# cpu-68010.net
KiCad netlist of a schematic drawn in EAGLE
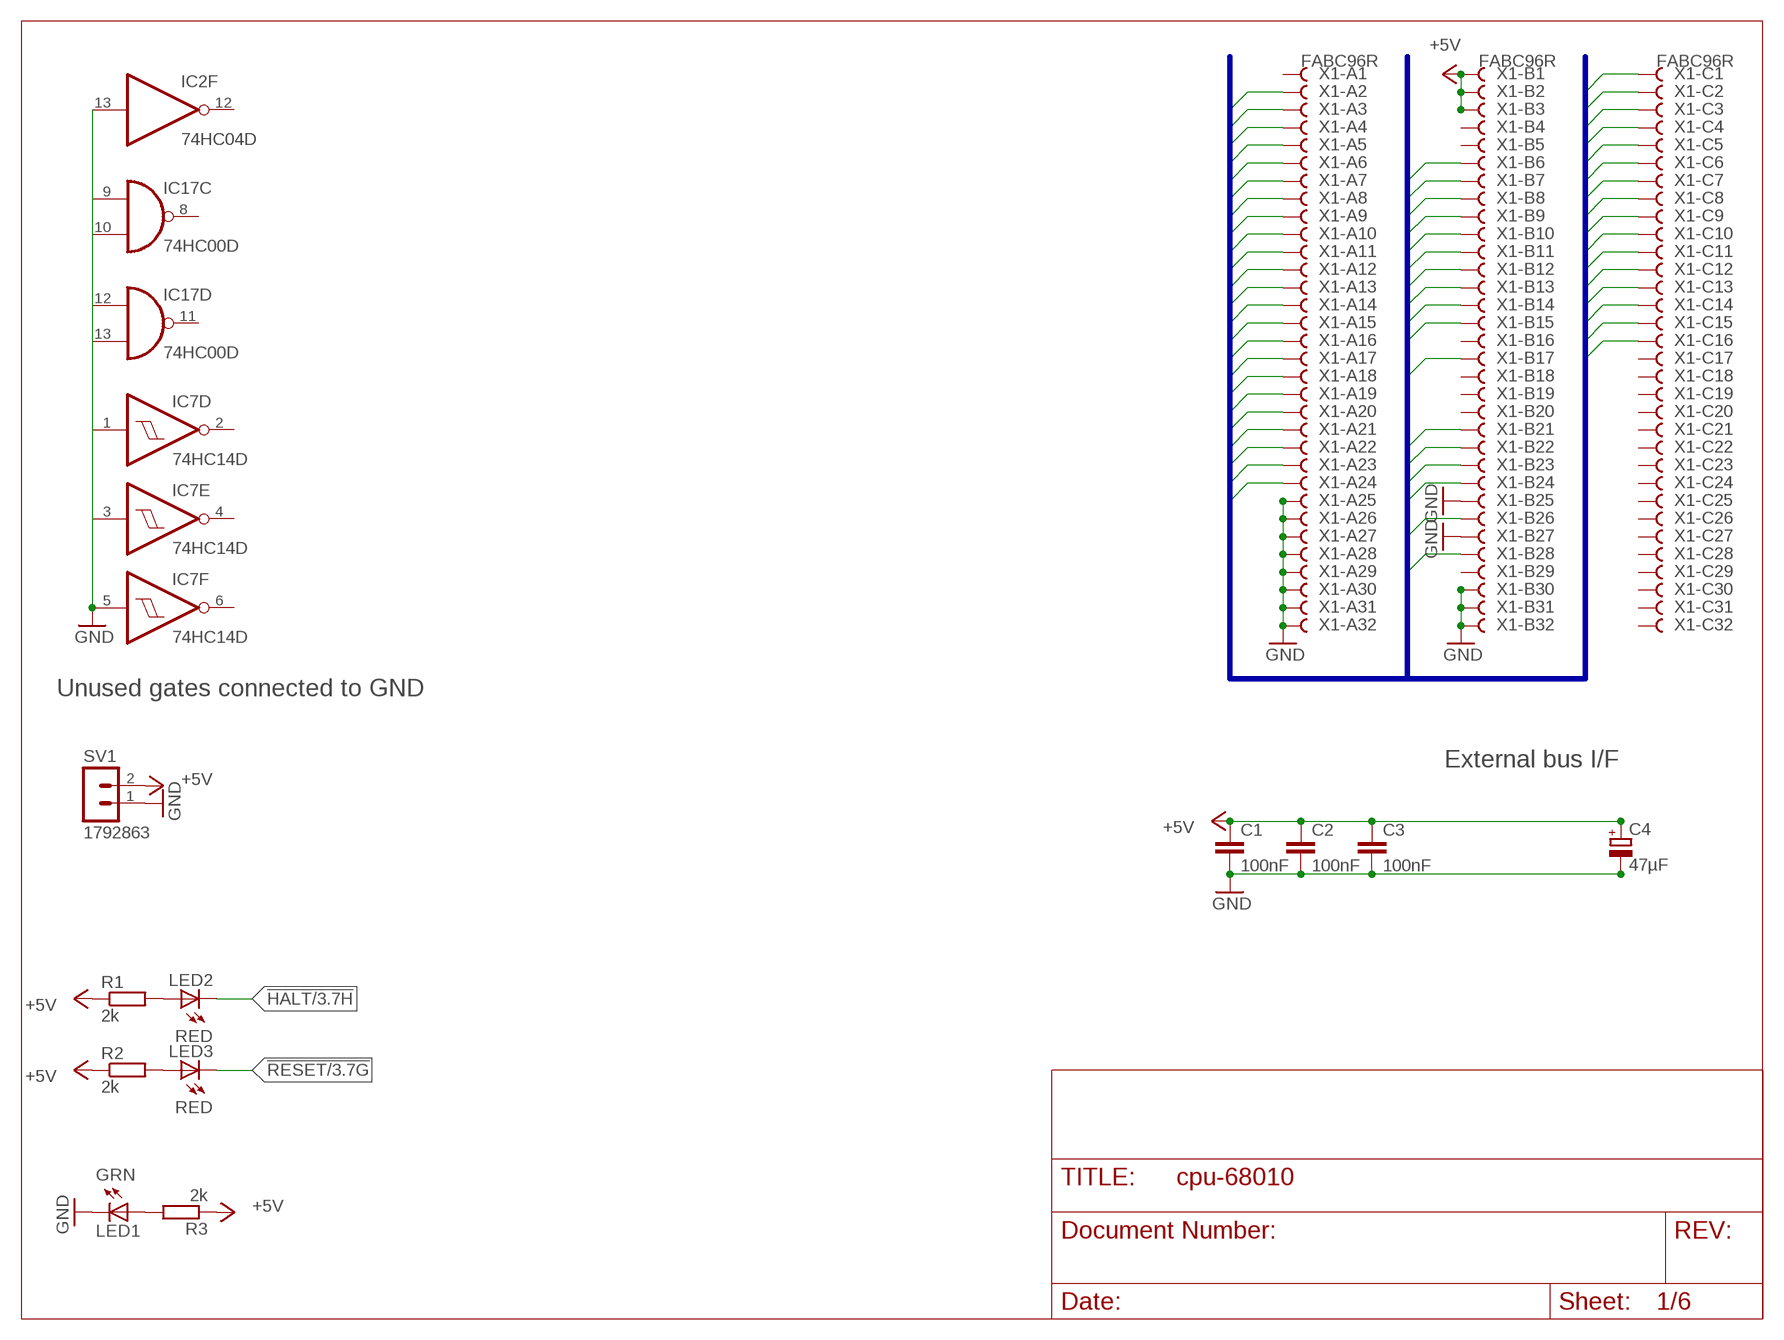
[diagram p0: schematic, sheet 1]
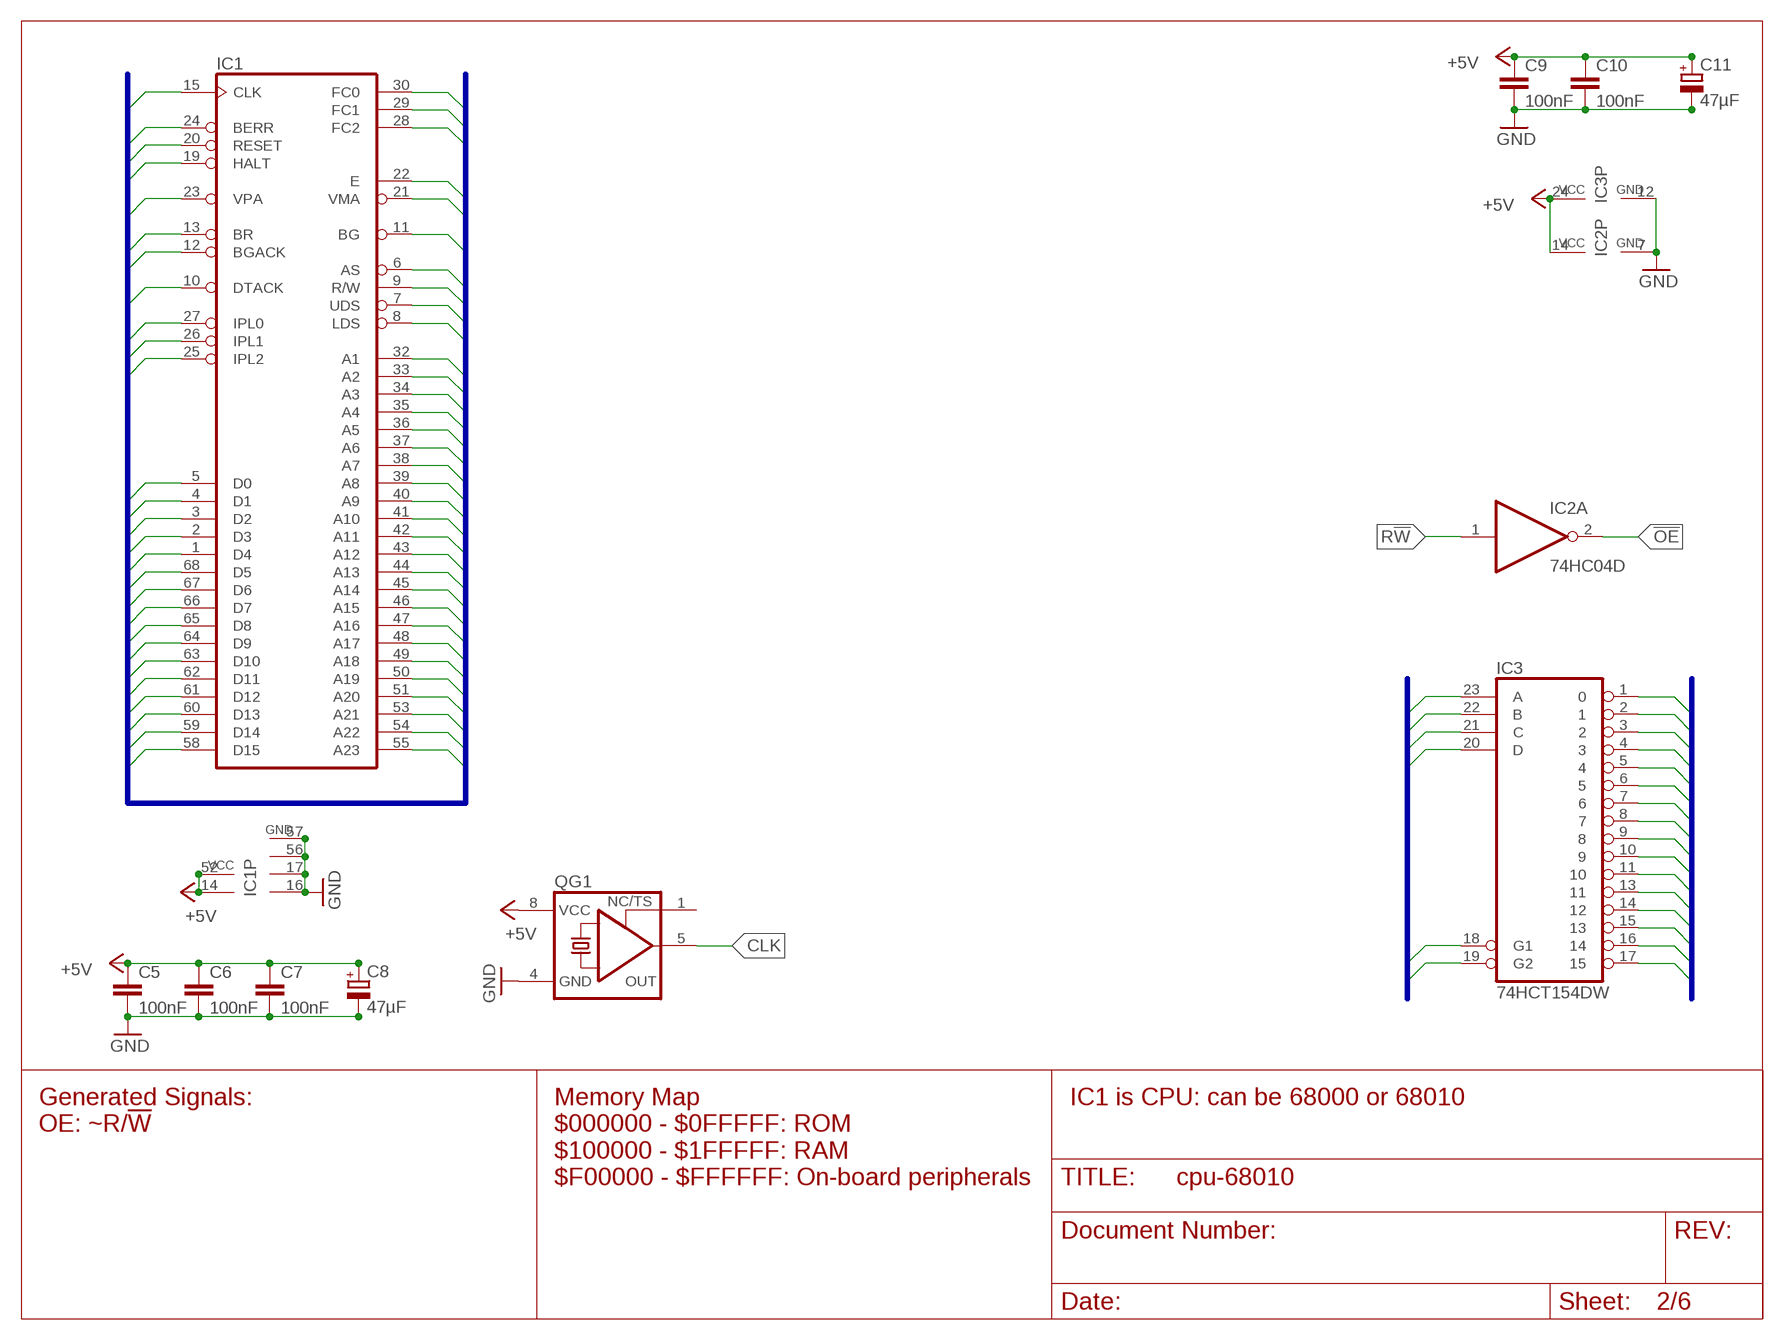
[diagram p1: schematic, sheet 2]
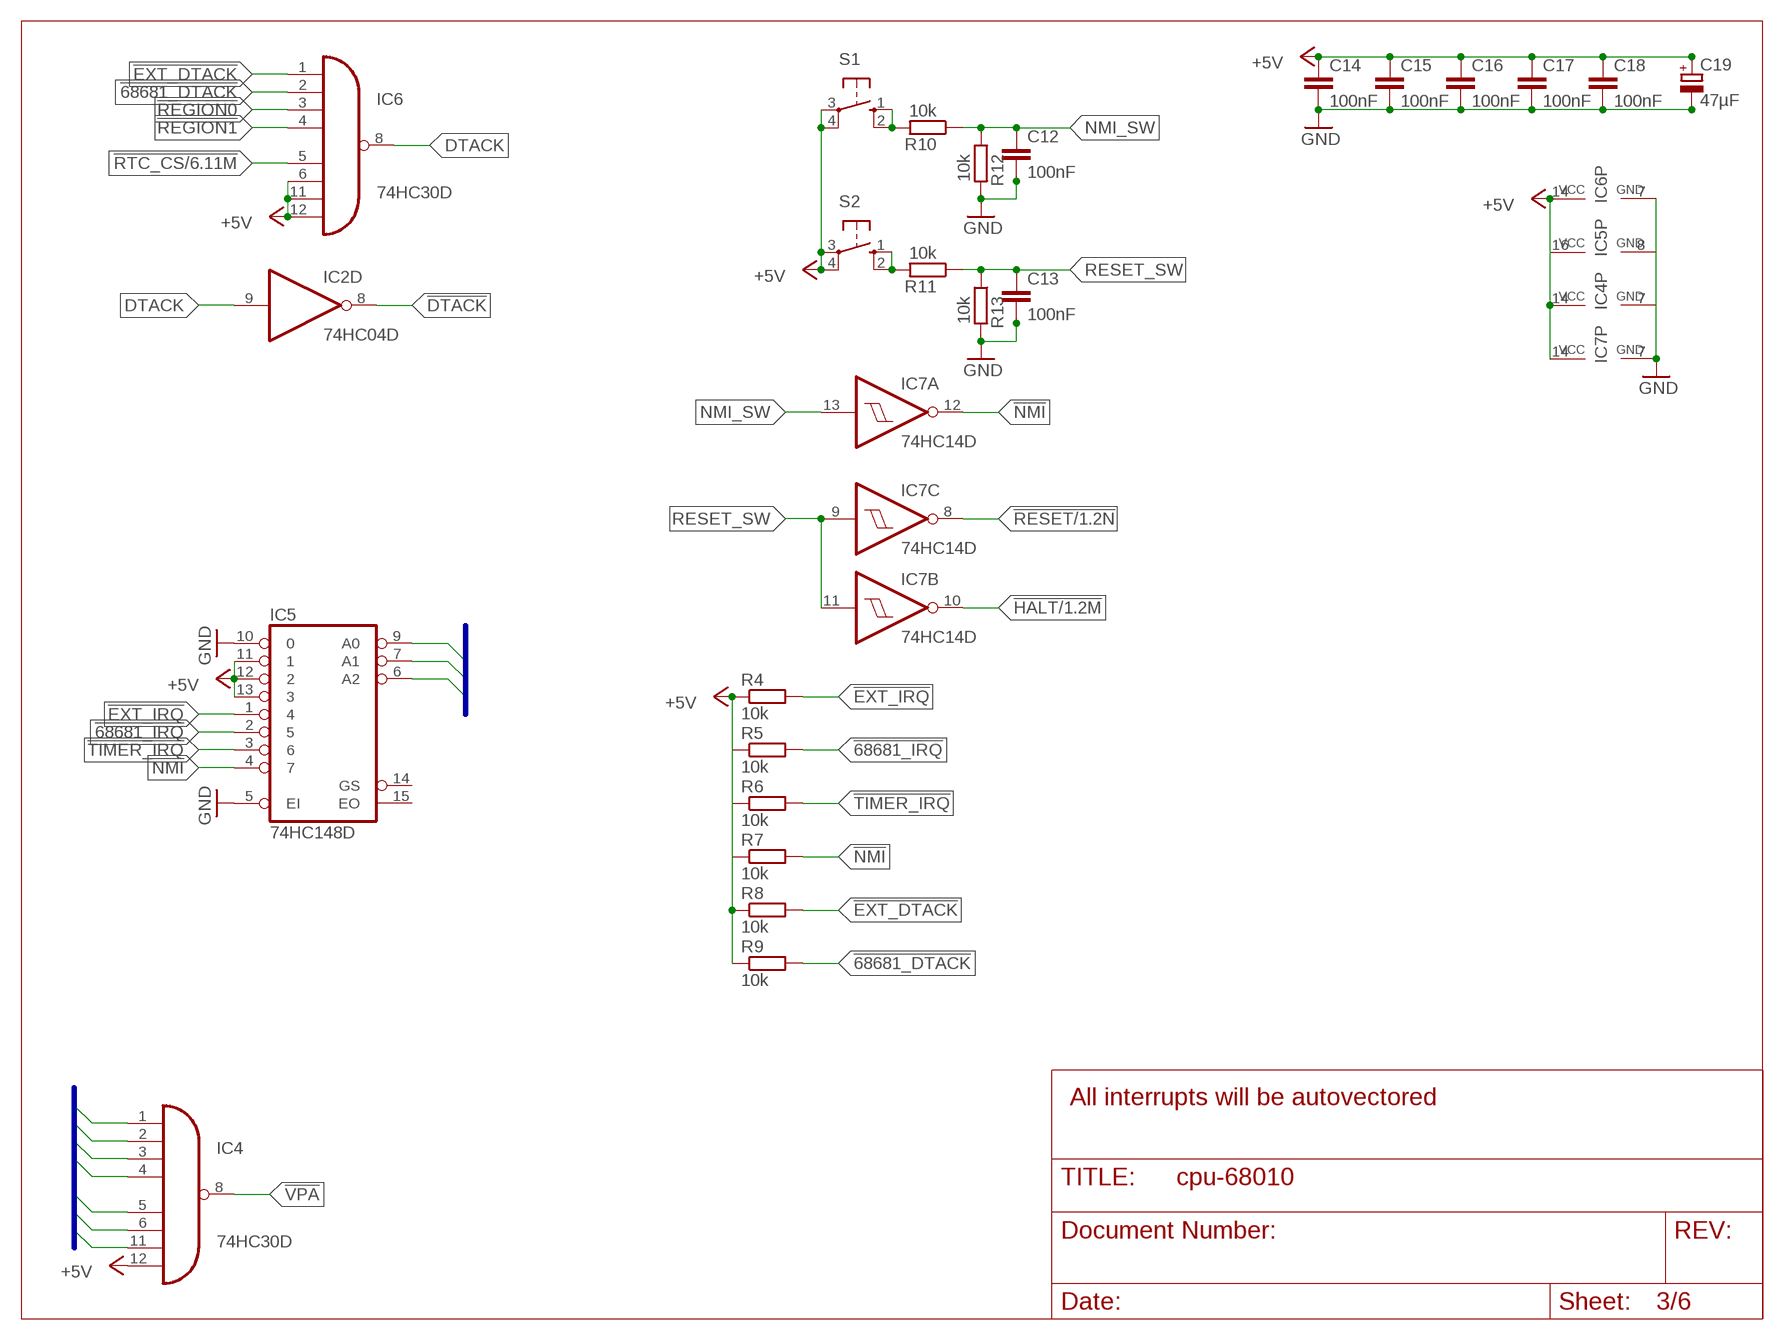
[diagram p2: schematic, sheet 3]
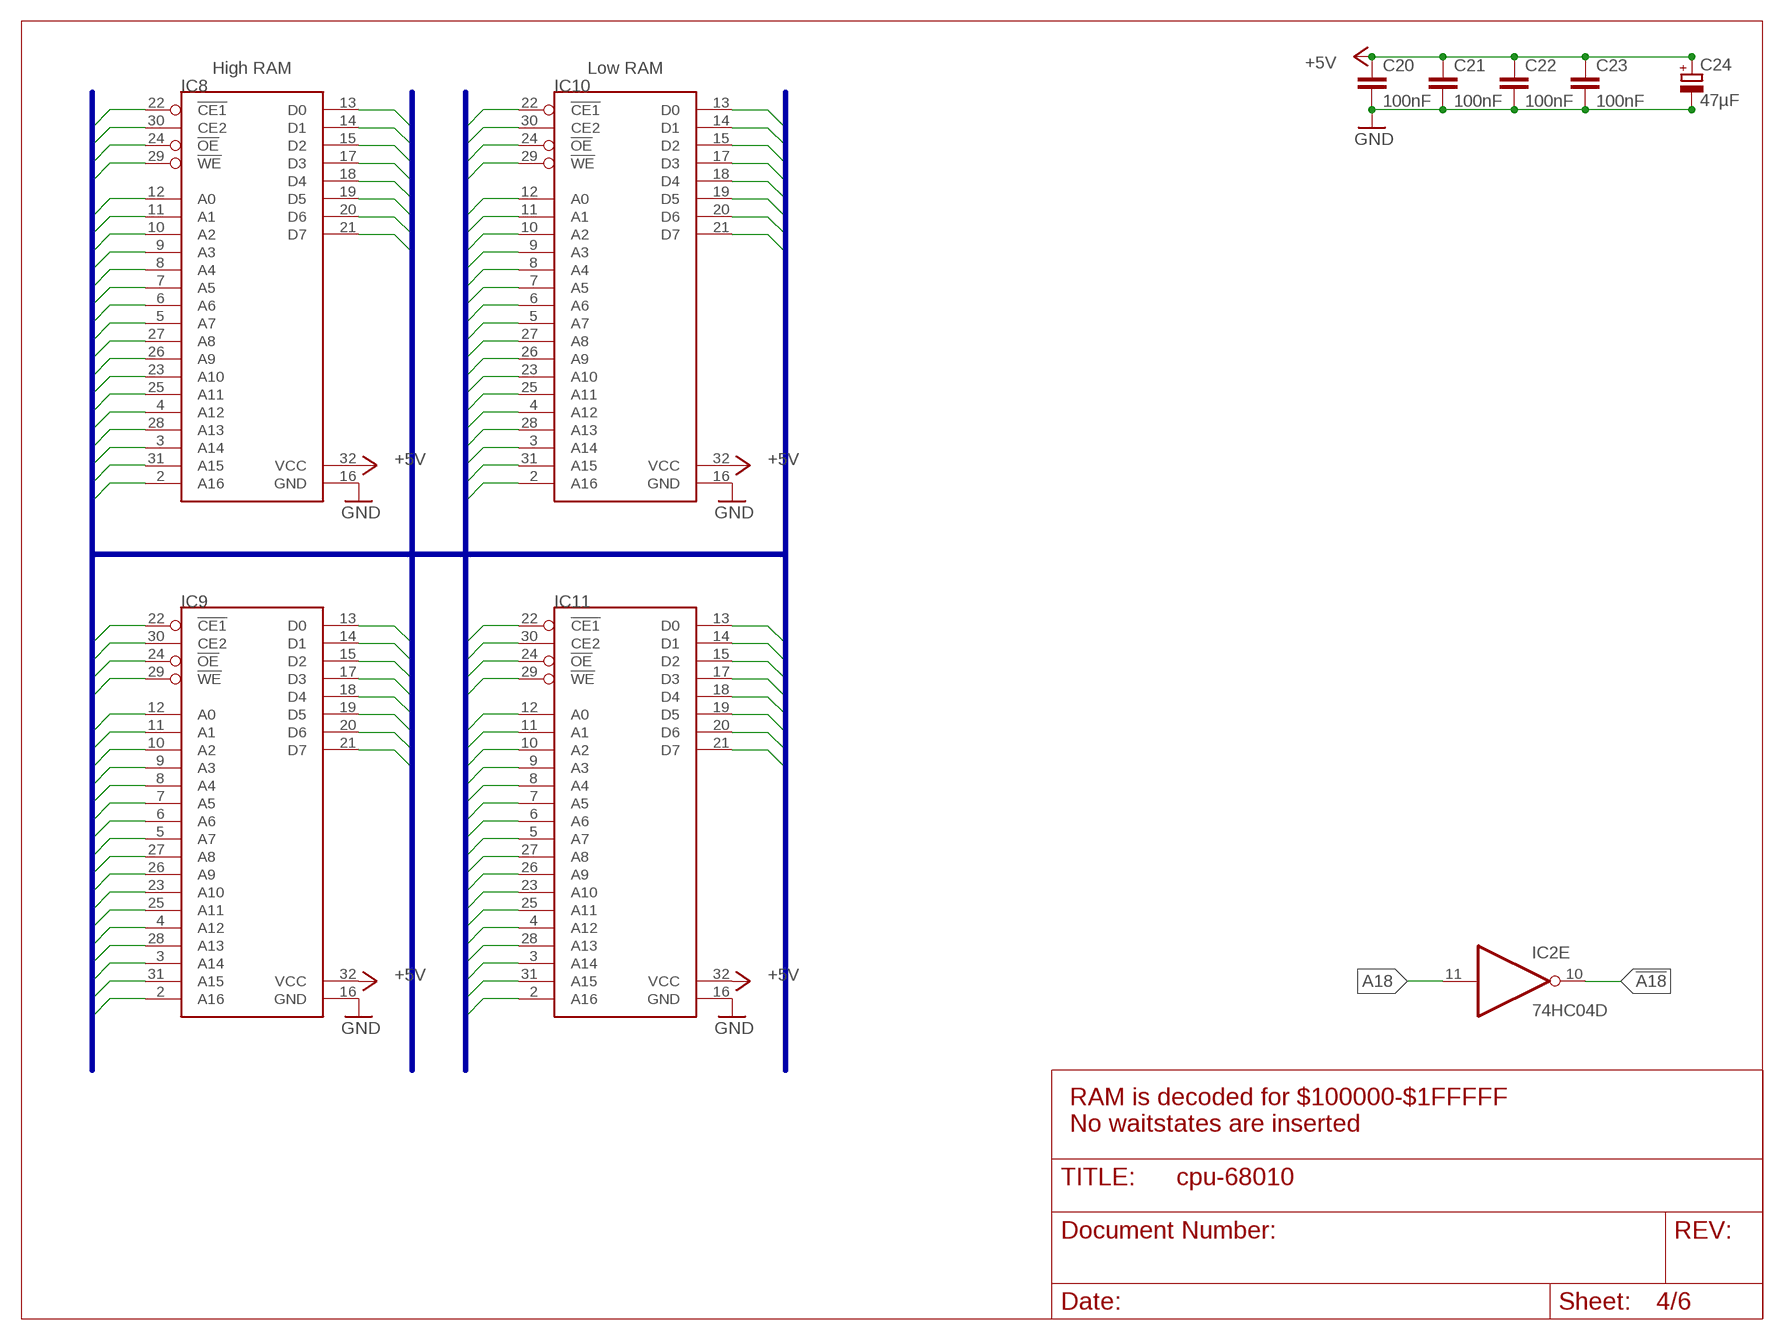
[diagram p3: schematic, sheet 4]
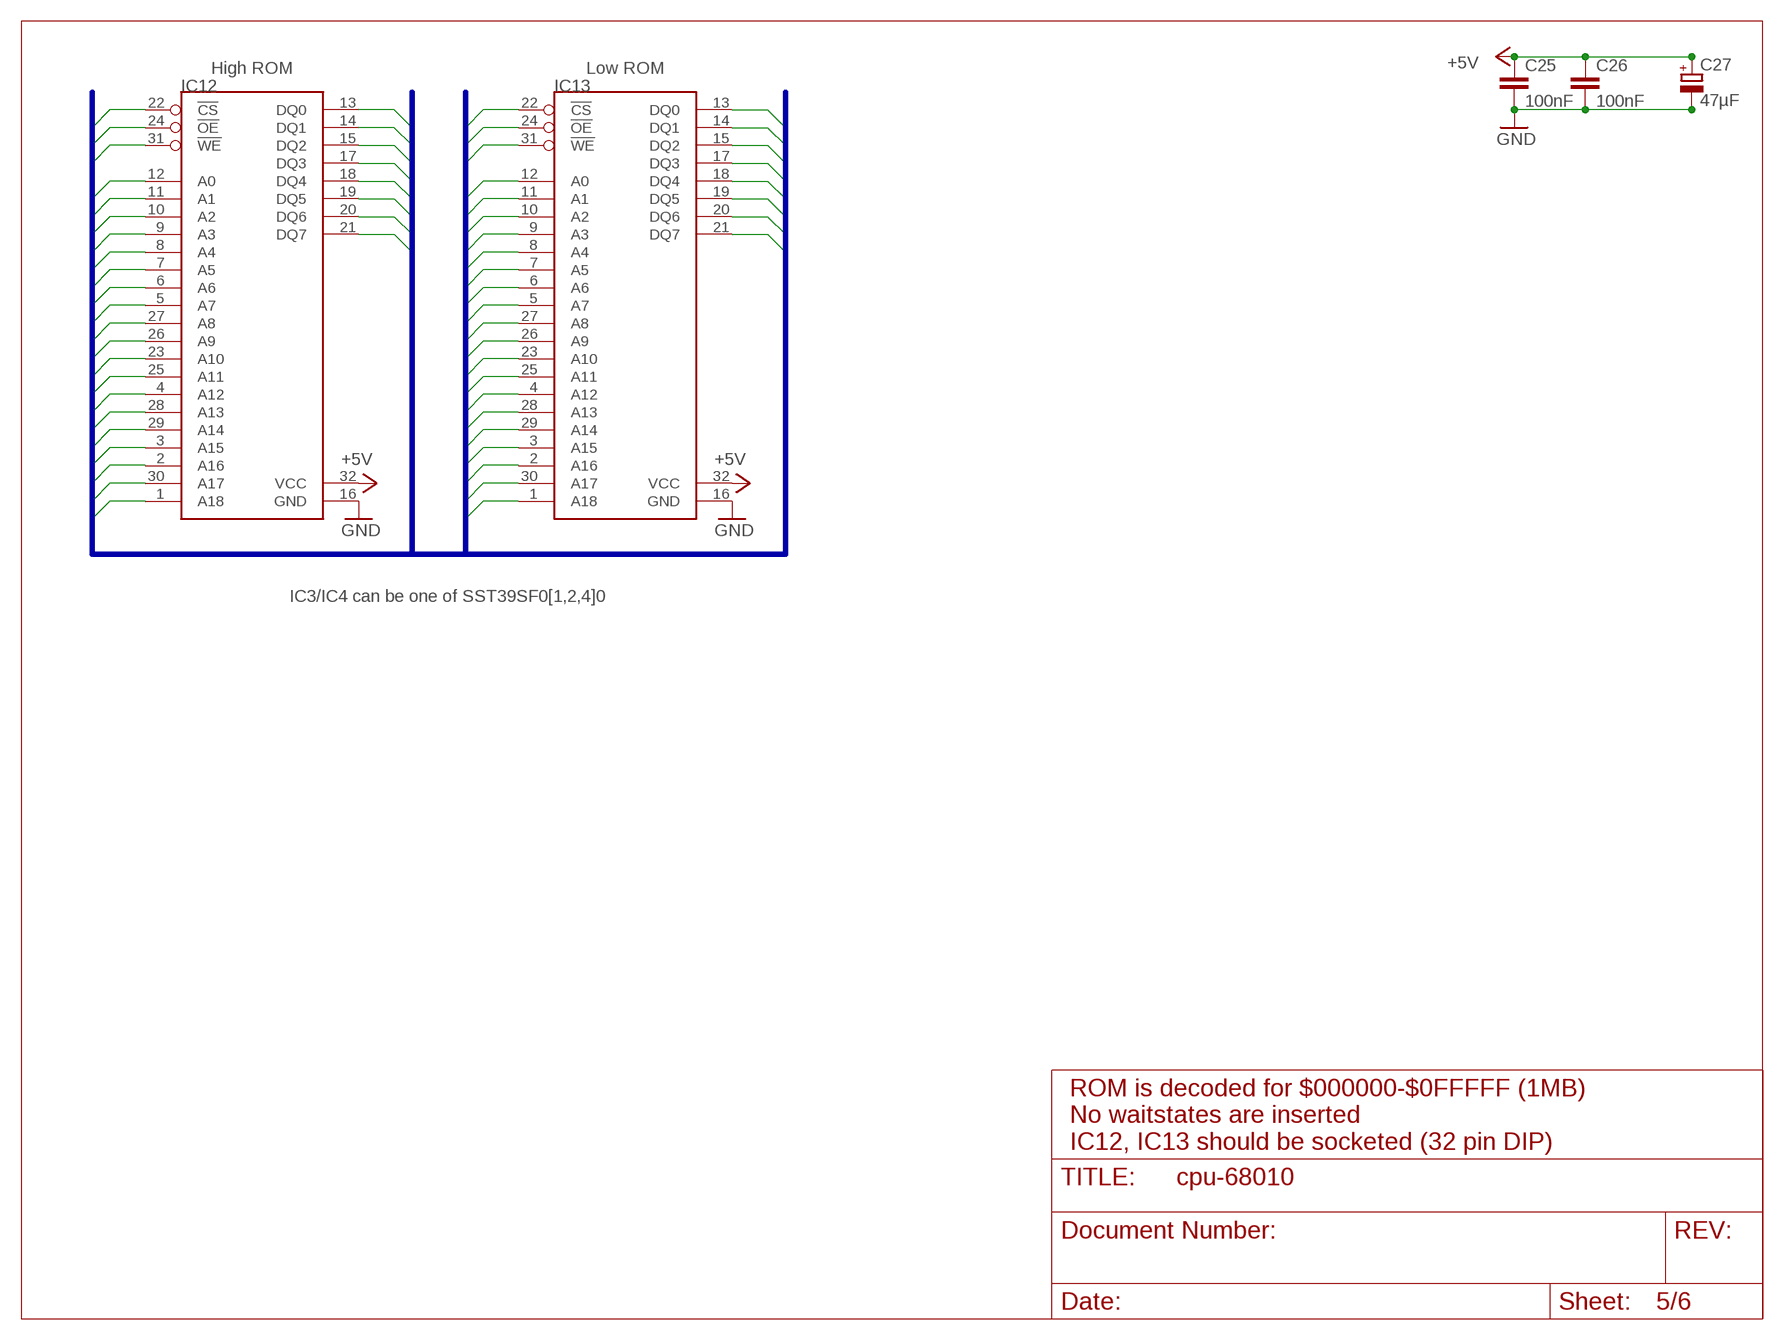
[diagram p4: schematic, sheet 5]
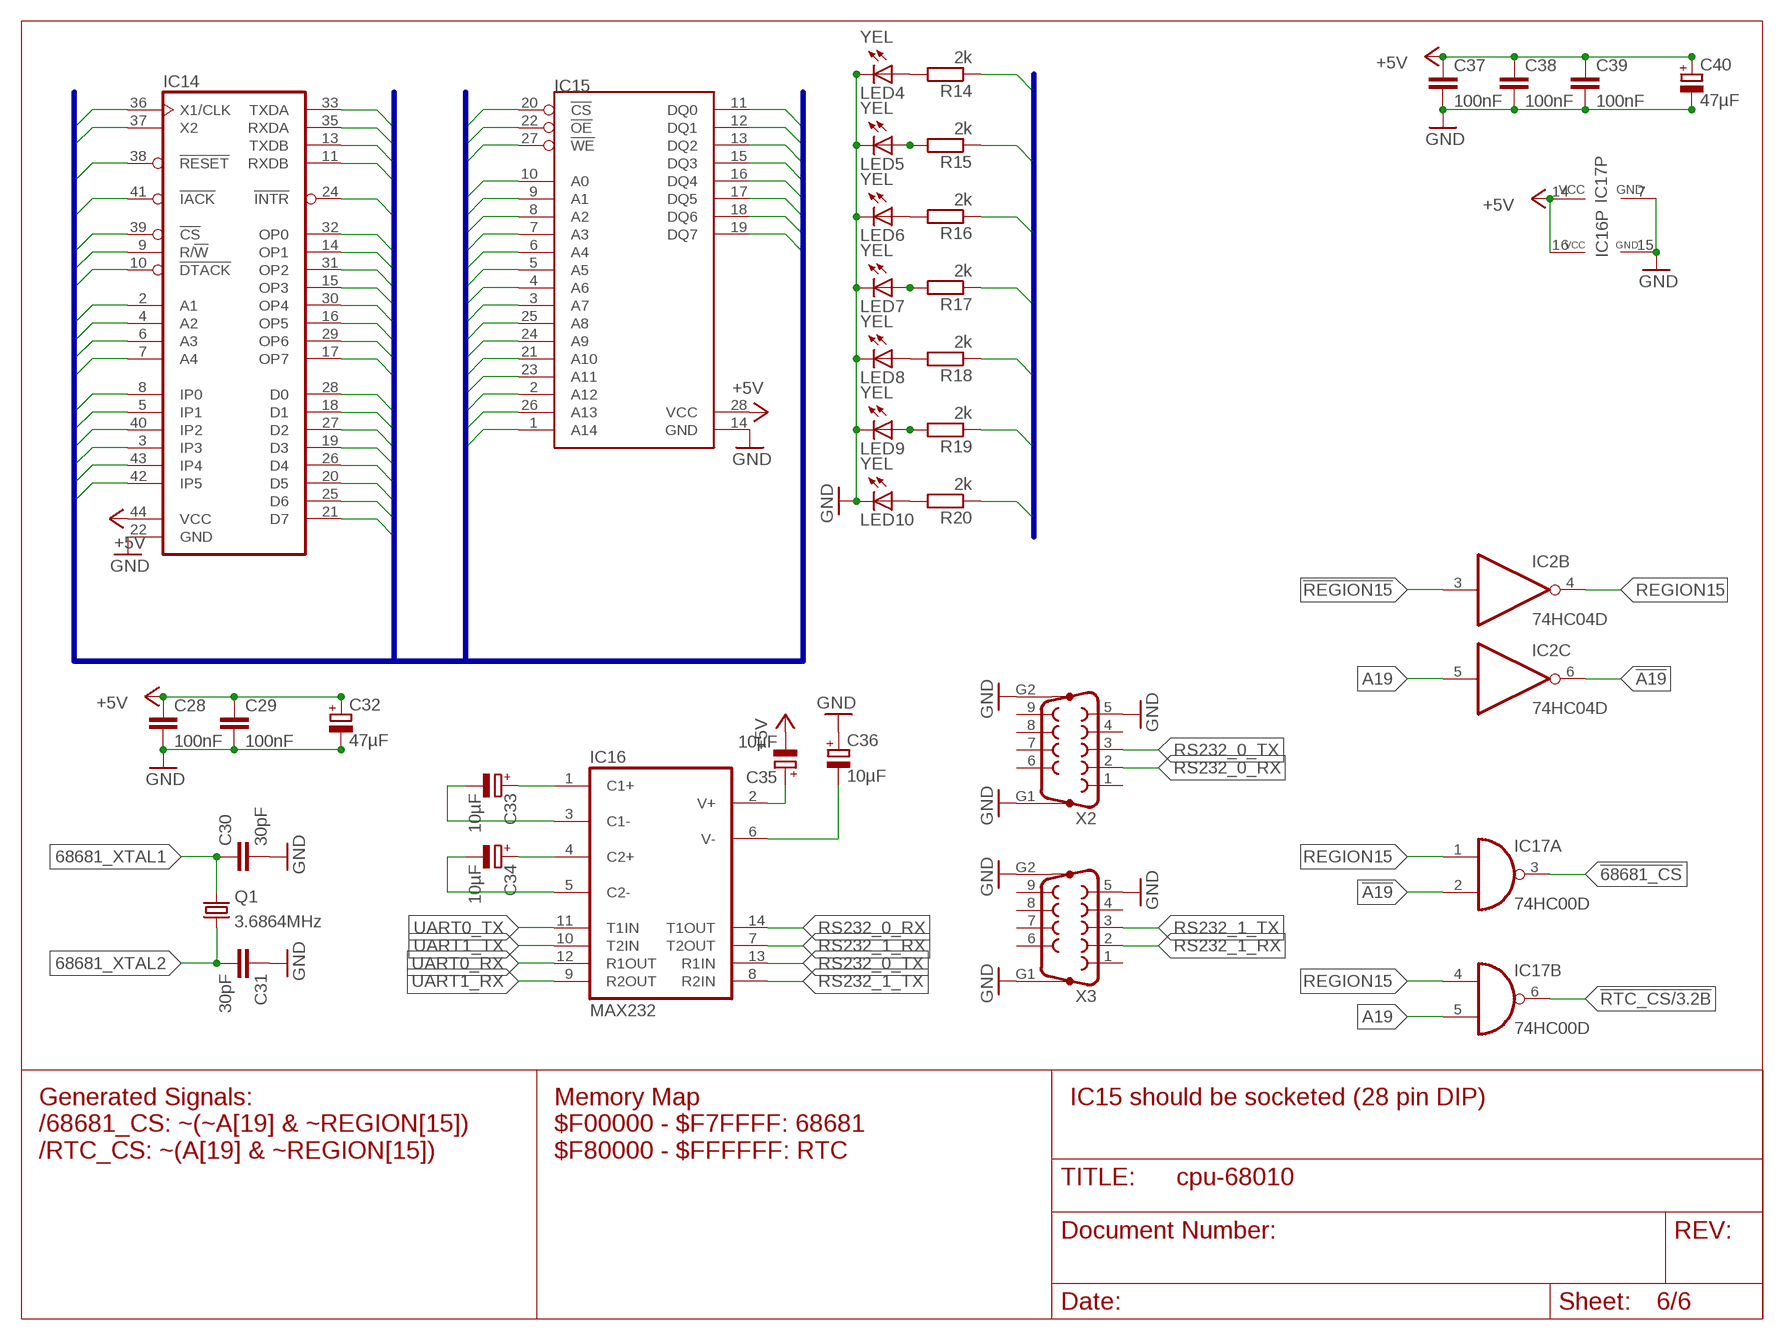
[diagram p5: schematic, sheet 6]

(export (version "E")
  (design (tool "Eeschema 10.0.6"))
  (components
    (comp (ref "C25")
      (value "100nF")
      (footprint "eagle-import:C0805")
      (libsource (lib "eagle-import") (part "C-EUC0805"))
    )
    (comp (ref "C26")
      (value "100nF")
      (footprint "eagle-import:C0805")
      (libsource (lib "eagle-import") (part "C-EUC0805"))
    )
    (comp (ref "C27")
      (value "47µF")
      (footprint "eagle-import:CT6032")
      (libsource (lib "eagle-import") (part "CPOL-EUCT6032"))
    )
    (comp (ref "IC12")
      (value "SST39SF0X0PDIP32")
      (footprint "eagle-import:DIL32")
      (libsource (lib "eagle-import") (part "SST39SF0X0PDIP32"))
    )
    (comp (ref "IC13")
      (value "SST39SF0X0PDIP32")
      (footprint "eagle-import:DIL32")
      (libsource (lib "eagle-import") (part "SST39SF0X0PDIP32"))
    )
    (comp (ref "C28")
      (value "100nF")
      (footprint "eagle-import:C0805")
      (libsource (lib "eagle-import") (part "C-EUC0805"))
    )
    (comp (ref "C29")
      (value "100nF")
      (footprint "eagle-import:C0805")
      (libsource (lib "eagle-import") (part "C-EUC0805"))
    )
    (comp (ref "C30")
      (value "30pF")
      (footprint "eagle-import:C0805")
      (libsource (lib "eagle-import") (part "C-EUC0805"))
    )
    (comp (ref "C31")
      (value "30pF")
      (footprint "eagle-import:C0805")
      (libsource (lib "eagle-import") (part "C-EUC0805"))
    )
    (comp (ref "C32")
      (value "47µF")
      (footprint "eagle-import:CT6032")
      (libsource (lib "eagle-import") (part "CPOL-EUCT6032"))
    )
    (comp (ref "C33")
      (value "10µF")
      (footprint "eagle-import:E1,8-4")
      (libsource (lib "eagle-import") (part "CPOL-EUE1.8-4"))
    )
    (comp (ref "C34")
      (value "10µF")
      (footprint "eagle-import:E1,8-4")
      (libsource (lib "eagle-import") (part "CPOL-EUE1.8-4"))
    )
    (comp (ref "C35")
      (value "10µF")
      (footprint "eagle-import:E1,8-4")
      (libsource (lib "eagle-import") (part "CPOL-EUE1.8-4"))
    )
    (comp (ref "C36")
      (value "10µF")
      (footprint "eagle-import:E1,8-4")
      (libsource (lib "eagle-import") (part "CPOL-EUE1.8-4"))
    )
    (comp (ref "C37")
      (value "100nF")
      (footprint "eagle-import:C0805")
      (libsource (lib "eagle-import") (part "C-EUC0805"))
    )
    (comp (ref "C38")
      (value "100nF")
      (footprint "eagle-import:C0805")
      (libsource (lib "eagle-import") (part "C-EUC0805"))
    )
    (comp (ref "C39")
      (value "100nF")
      (footprint "eagle-import:C0805")
      (libsource (lib "eagle-import") (part "C-EUC0805"))
    )
    (comp (ref "C40")
      (value "47µF")
      (footprint "eagle-import:CT6032")
      (libsource (lib "eagle-import") (part "CPOL-EUCT6032"))
    )
    (comp (ref "IC2")
      (value "74HC04D")
      (footprint "eagle-import:SO14")
      (libsource (lib "eagle-import") (part "7404DHC"))
    )
    (comp (ref "IC14")
      (value "MC68681PLCC44-SOCKET")
      (footprint "eagle-import:PLCC-S44")
      (libsource (lib "eagle-import") (part "MC68681PLCC44-SOCKET"))
    )
    (comp (ref "IC15")
      (value "DS1244EDIP-28")
      (footprint "eagle-import:DIL28-6")
      (libsource (lib "eagle-import") (part "DS1244EDIP-28"))
    )
    (comp (ref "IC16")
      (value "MAX232")
      (footprint "eagle-import:DIL16")
      (fields (field (name "MF") "MAXIM") (field (name "MPN") "MAX232ACPE+"))
      (libsource (lib "eagle-import") (part "MAX232"))
    )
    (comp (ref "IC17")
      (value "74HC00D")
      (footprint "eagle-import:SO14")
      (libsource (lib "eagle-import") (part "7400DHC"))
    )
    (comp (ref "LED4")
      (value "YEL")
      (footprint "eagle-import:CHIPLED_1206")
      (libsource (lib "eagle-import") (part "LEDCHIPLED_1206"))
    )
    (comp (ref "LED5")
      (value "YEL")
      (footprint "eagle-import:CHIPLED_1206")
      (libsource (lib "eagle-import") (part "LEDCHIPLED_1206"))
    )
    (comp (ref "LED6")
      (value "YEL")
      (footprint "eagle-import:CHIPLED_1206")
      (libsource (lib "eagle-import") (part "LEDCHIPLED_1206"))
    )
    (comp (ref "LED7")
      (value "YEL")
      (footprint "eagle-import:CHIPLED_1206")
      (libsource (lib "eagle-import") (part "LEDCHIPLED_1206"))
    )
    (comp (ref "LED8")
      (value "YEL")
      (footprint "eagle-import:CHIPLED_1206")
      (libsource (lib "eagle-import") (part "LEDCHIPLED_1206"))
    )
    (comp (ref "LED9")
      (value "YEL")
      (footprint "eagle-import:CHIPLED_1206")
      (libsource (lib "eagle-import") (part "LEDCHIPLED_1206"))
    )
    (comp (ref "LED10")
      (value "YEL")
      (footprint "eagle-import:CHIPLED_1206")
      (libsource (lib "eagle-import") (part "LEDCHIPLED_1206"))
    )
    (comp (ref "Q1")
      (value "3.6864MHz")
      (footprint "eagle-import:HC49_S")
      (libsource (lib "eagle-import") (part "CRYSTALHC49S"))
    )
    (comp (ref "R14")
      (value "2k")
      (footprint "eagle-import:M0805")
      (libsource (lib "eagle-import") (part "R-EU_M0805"))
    )
    (comp (ref "R15")
      (value "2k")
      (footprint "eagle-import:M0805")
      (libsource (lib "eagle-import") (part "R-EU_M0805"))
    )
    (comp (ref "R16")
      (value "2k")
      (footprint "eagle-import:M0805")
      (libsource (lib "eagle-import") (part "R-EU_M0805"))
    )
    (comp (ref "R17")
      (value "2k")
      (footprint "eagle-import:M0805")
      (libsource (lib "eagle-import") (part "R-EU_M0805"))
    )
    (comp (ref "R18")
      (value "2k")
      (footprint "eagle-import:M0805")
      (libsource (lib "eagle-import") (part "R-EU_M0805"))
    )
    (comp (ref "R19")
      (value "2k")
      (footprint "eagle-import:M0805")
      (libsource (lib "eagle-import") (part "R-EU_M0805"))
    )
    (comp (ref "R20")
      (value "2k")
      (footprint "eagle-import:M0805")
      (libsource (lib "eagle-import") (part "R-EU_M0805"))
    )
    (comp (ref "X2")
      (value "F09HP")
      (footprint "eagle-import:F09HP")
      (libsource (lib "eagle-import") (part "F09HP"))
    )
    (comp (ref "X3")
      (value "F09HP")
      (footprint "eagle-import:F09HP")
      (libsource (lib "eagle-import") (part "F09HP"))
    )
    (comp (ref "C12")
      (value "100nF")
      (footprint "eagle-import:C0805")
      (libsource (lib "eagle-import") (part "C-EUC0805"))
    )
    (comp (ref "C13")
      (value "100nF")
      (footprint "eagle-import:C0805")
      (libsource (lib "eagle-import") (part "C-EUC0805"))
    )
    (comp (ref "C14")
      (value "100nF")
      (footprint "eagle-import:C0805")
      (libsource (lib "eagle-import") (part "C-EUC0805"))
    )
    (comp (ref "C15")
      (value "100nF")
      (footprint "eagle-import:C0805")
      (libsource (lib "eagle-import") (part "C-EUC0805"))
    )
    (comp (ref "C16")
      (value "100nF")
      (footprint "eagle-import:C0805")
      (libsource (lib "eagle-import") (part "C-EUC0805"))
    )
    (comp (ref "C17")
      (value "100nF")
      (footprint "eagle-import:C0805")
      (libsource (lib "eagle-import") (part "C-EUC0805"))
    )
    (comp (ref "C18")
      (value "100nF")
      (footprint "eagle-import:C0805")
      (libsource (lib "eagle-import") (part "C-EUC0805"))
    )
    (comp (ref "C19")
      (value "47µF")
      (footprint "eagle-import:CT6032")
      (libsource (lib "eagle-import") (part "CPOL-EUCT6032"))
    )
    (comp (ref "IC4")
      (value "74HC30D")
      (footprint "eagle-import:SO14")
      (libsource (lib "eagle-import") (part "7430DHC"))
    )
    (comp (ref "IC5")
      (value "74HC148D")
      (footprint "eagle-import:SO16")
      (libsource (lib "eagle-import") (part "74148DHC"))
    )
    (comp (ref "IC6")
      (value "74HC30D")
      (footprint "eagle-import:SO14")
      (libsource (lib "eagle-import") (part "7430DHC"))
    )
    (comp (ref "IC7")
      (value "74HC14D")
      (footprint "eagle-import:SO14")
      (libsource (lib "eagle-import") (part "7414DHC"))
    )
    (comp (ref "R4")
      (value "10k")
      (footprint "eagle-import:M0805")
      (libsource (lib "eagle-import") (part "R-EU_M0805"))
    )
    (comp (ref "R5")
      (value "10k")
      (footprint "eagle-import:M0805")
      (libsource (lib "eagle-import") (part "R-EU_M0805"))
    )
    (comp (ref "R6")
      (value "10k")
      (footprint "eagle-import:M0805")
      (libsource (lib "eagle-import") (part "R-EU_M0805"))
    )
    (comp (ref "R7")
      (value "10k")
      (footprint "eagle-import:M0805")
      (libsource (lib "eagle-import") (part "R-EU_M0805"))
    )
    (comp (ref "R8")
      (value "10k")
      (footprint "eagle-import:M0805")
      (libsource (lib "eagle-import") (part "R-EU_M0805"))
    )
    (comp (ref "R9")
      (value "10k")
      (footprint "eagle-import:M0805")
      (libsource (lib "eagle-import") (part "R-EU_M0805"))
    )
    (comp (ref "R10")
      (value "10k")
      (footprint "eagle-import:M0805")
      (libsource (lib "eagle-import") (part "R-EU_M0805"))
    )
    (comp (ref "R11")
      (value "10k")
      (footprint "eagle-import:M0805")
      (libsource (lib "eagle-import") (part "R-EU_M0805"))
    )
    (comp (ref "R12")
      (value "10k")
      (footprint "eagle-import:M0805")
      (libsource (lib "eagle-import") (part "R-EU_M0805"))
    )
    (comp (ref "R13")
      (value "10k")
      (footprint "eagle-import:M0805")
      (libsource (lib "eagle-import") (part "R-EU_M0805"))
    )
    (comp (ref "S1")
      (value "10-XX")
      (footprint "eagle-import:B3F-10XX")
      (fields (field (name "MPN") "B3F-1000"))
      (libsource (lib "eagle-import") (part "10-XX"))
    )
    (comp (ref "S2")
      (value "10-XX")
      (footprint "eagle-import:B3F-10XX")
      (fields (field (name "MPN") "B3F-1000"))
      (libsource (lib "eagle-import") (part "10-XX"))
    )
    (comp (ref "C20")
      (value "100nF")
      (footprint "eagle-import:C0805")
      (libsource (lib "eagle-import") (part "C-EUC0805"))
    )
    (comp (ref "C21")
      (value "100nF")
      (footprint "eagle-import:C0805")
      (libsource (lib "eagle-import") (part "C-EUC0805"))
    )
    (comp (ref "C22")
      (value "100nF")
      (footprint "eagle-import:C0805")
      (libsource (lib "eagle-import") (part "C-EUC0805"))
    )
    (comp (ref "C23")
      (value "100nF")
      (footprint "eagle-import:C0805")
      (libsource (lib "eagle-import") (part "C-EUC0805"))
    )
    (comp (ref "C24")
      (value "47µF")
      (footprint "eagle-import:CT6032")
      (libsource (lib "eagle-import") (part "CPOL-EUCT6032"))
    )
    (comp (ref "IC8")
      (value "CY62128BSOIC32")
      (footprint "eagle-import:SO32X")
      (libsource (lib "eagle-import") (part "CY62128BSOIC32"))
    )
    (comp (ref "IC9")
      (value "CY62128BSOIC32")
      (footprint "eagle-import:SO32X")
      (libsource (lib "eagle-import") (part "CY62128BSOIC32"))
    )
    (comp (ref "IC10")
      (value "CY62128BSOIC32")
      (footprint "eagle-import:SO32X")
      (libsource (lib "eagle-import") (part "CY62128BSOIC32"))
    )
    (comp (ref "IC11")
      (value "CY62128BSOIC32")
      (footprint "eagle-import:SO32X")
      (libsource (lib "eagle-import") (part "CY62128BSOIC32"))
    )
    (comp (ref "C1")
      (value "100nF")
      (footprint "eagle-import:C0805")
      (libsource (lib "eagle-import") (part "C-EUC0805"))
    )
    (comp (ref "C2")
      (value "100nF")
      (footprint "eagle-import:C0805")
      (libsource (lib "eagle-import") (part "C-EUC0805"))
    )
    (comp (ref "C3")
      (value "100nF")
      (footprint "eagle-import:C0805")
      (libsource (lib "eagle-import") (part "C-EUC0805"))
    )
    (comp (ref "C4")
      (value "47µF")
      (footprint "eagle-import:CT6032")
      (libsource (lib "eagle-import") (part "CPOL-EUCT6032"))
    )
    (comp (ref "LED1")
      (value "GRN")
      (footprint "eagle-import:CHIPLED_1206")
      (libsource (lib "eagle-import") (part "LEDCHIPLED_1206"))
    )
    (comp (ref "LED2")
      (value "RED")
      (footprint "eagle-import:CHIPLED_1206")
      (libsource (lib "eagle-import") (part "LEDCHIPLED_1206"))
    )
    (comp (ref "LED3")
      (value "RED")
      (footprint "eagle-import:CHIPLED_1206")
      (libsource (lib "eagle-import") (part "LEDCHIPLED_1206"))
    )
    (comp (ref "R1")
      (value "2k")
      (footprint "eagle-import:M0805")
      (libsource (lib "eagle-import") (part "R-EU_M0805"))
    )
    (comp (ref "R2")
      (value "2k")
      (footprint "eagle-import:M0805")
      (libsource (lib "eagle-import") (part "R-EU_M0805"))
    )
    (comp (ref "R3")
      (value "2k")
      (footprint "eagle-import:M0805")
      (libsource (lib "eagle-import") (part "R-EU_M0805"))
    )
    (comp (ref "SV1")
      (value "1792863")
      (footprint "eagle-import:1792863")
      (libsource (lib "eagle-import") (part "1792863"))
    )
    (comp (ref "X1")
      (value "FABC96R")
      (footprint "eagle-import:FABC96R")
      (libsource (lib "eagle-import") (part "FABC96R"))
    )
    (comp (ref "C5")
      (value "100nF")
      (footprint "eagle-import:C0805")
      (libsource (lib "eagle-import") (part "C-EUC0805"))
    )
    (comp (ref "C6")
      (value "100nF")
      (footprint "eagle-import:C0805")
      (libsource (lib "eagle-import") (part "C-EUC0805"))
    )
    (comp (ref "C7")
      (value "100nF")
      (footprint "eagle-import:C0805")
      (libsource (lib "eagle-import") (part "C-EUC0805"))
    )
    (comp (ref "C8")
      (value "47µF")
      (footprint "eagle-import:CT6032")
      (libsource (lib "eagle-import") (part "CPOL-EUCT6032"))
    )
    (comp (ref "C9")
      (value "100nF")
      (footprint "eagle-import:C0805")
      (libsource (lib "eagle-import") (part "C-EUC0805"))
    )
    (comp (ref "C10")
      (value "100nF")
      (footprint "eagle-import:C0805")
      (libsource (lib "eagle-import") (part "C-EUC0805"))
    )
    (comp (ref "C11")
      (value "47µF")
      (footprint "eagle-import:CT6032")
      (libsource (lib "eagle-import") (part "CPOL-EUCT6032"))
    )
    (comp (ref "IC1")
      (value "MC68000FN-SOC")
      (footprint "eagle-import:PLCC68SOCK")
      (libsource (lib "eagle-import") (part "MC68000FN-SOC"))
    )
    (comp (ref "IC3")
      (value "74HCT154DW")
      (footprint "eagle-import:SO24W")
      (libsource (lib "eagle-import") (part "74154DWHCT"))
    )
    (comp (ref "QG1")
      (value "XO-8")
      (footprint "eagle-import:DIL08S")
      (libsource (lib "eagle-import") (part "XO-8"))
    )
  )
  (nets
    (net (code "1") (name "+5V") (class "Default")
      (node (ref "C1") (pin "1") (pinfunction "1_1") (pintype "passive"))
      (node (ref "C10") (pin "1") (pinfunction "1_1") (pintype "passive"))
      (node (ref "C11") (pin "+") (pinfunction "+_+") (pintype "passive"))
      (node (ref "C14") (pin "1") (pinfunction "1_1") (pintype "passive"))
      (node (ref "C15") (pin "1") (pinfunction "1_1") (pintype "passive"))
      (node (ref "C16") (pin "1") (pinfunction "1_1") (pintype "passive"))
      (node (ref "C17") (pin "1") (pinfunction "1_1") (pintype "passive"))
      (node (ref "C18") (pin "1") (pinfunction "1_1") (pintype "passive"))
      (node (ref "C19") (pin "+") (pinfunction "+_+") (pintype "passive"))
      (node (ref "C2") (pin "1") (pinfunction "1_1") (pintype "passive"))
      (node (ref "C20") (pin "1") (pinfunction "1_1") (pintype "passive"))
      (node (ref "C21") (pin "1") (pinfunction "1_1") (pintype "passive"))
      (node (ref "C22") (pin "1") (pinfunction "1_1") (pintype "passive"))
      (node (ref "C23") (pin "1") (pinfunction "1_1") (pintype "passive"))
      (node (ref "C24") (pin "+") (pinfunction "+_+") (pintype "passive"))
      (node (ref "C25") (pin "1") (pinfunction "1_1") (pintype "passive"))
      (node (ref "C26") (pin "1") (pinfunction "1_1") (pintype "passive"))
      (node (ref "C27") (pin "+") (pinfunction "+_+") (pintype "passive"))
      (node (ref "C28") (pin "1") (pinfunction "1_1") (pintype "passive"))
      (node (ref "C29") (pin "1") (pinfunction "1_1") (pintype "passive"))
      (node (ref "C3") (pin "1") (pinfunction "1_1") (pintype "passive"))
      (node (ref "C32") (pin "+") (pinfunction "+_+") (pintype "passive"))
      (node (ref "C35") (pin "-") (pinfunction "-_-") (pintype "passive"))
      (node (ref "C37") (pin "1") (pinfunction "1_1") (pintype "passive"))
      (node (ref "C38") (pin "1") (pinfunction "1_1") (pintype "passive"))
      (node (ref "C39") (pin "1") (pinfunction "1_1") (pintype "passive"))
      (node (ref "C4") (pin "+") (pinfunction "+_+") (pintype "passive"))
      (node (ref "C40") (pin "+") (pinfunction "+_+") (pintype "passive"))
      (node (ref "C5") (pin "1") (pinfunction "1_1") (pintype "passive"))
      (node (ref "C6") (pin "1") (pinfunction "1_1") (pintype "passive"))
      (node (ref "C7") (pin "1") (pinfunction "1_1") (pintype "passive"))
      (node (ref "C8") (pin "+") (pinfunction "+_+") (pintype "passive"))
      (node (ref "C9") (pin "1") (pinfunction "1_1") (pintype "passive"))
      (node (ref "IC1") (pin "14") (pinfunction "VCC_14") (pintype "power_in"))
      (node (ref "IC1") (pin "52") (pinfunction "VCC_52") (pintype "power_in"))
      (node (ref "IC10") (pin "32") (pinfunction "VCC_32") (pintype "power_in"))
      (node (ref "IC11") (pin "32") (pinfunction "VCC_32") (pintype "power_in"))
      (node (ref "IC12") (pin "32") (pinfunction "VCC_32") (pintype "power_in"))
      (node (ref "IC13") (pin "32") (pinfunction "VCC_32") (pintype "power_in"))
      (node (ref "IC14") (pin "44") (pinfunction "VCC_44") (pintype "power_in"))
      (node (ref "IC15") (pin "28") (pinfunction "VCC_28") (pintype "power_in"))
      (node (ref "IC16") (pin "16") (pinfunction "VCC_16") (pintype "power_in"))
      (node (ref "IC17") (pin "14") (pinfunction "VCC_14") (pintype "power_in"))
      (node (ref "IC2") (pin "14") (pinfunction "VCC_14") (pintype "power_in"))
      (node (ref "IC3") (pin "24") (pinfunction "VCC_24") (pintype "power_in"))
      (node (ref "IC4") (pin "12") (pinfunction "I7_12") (pintype "input"))
      (node (ref "IC4") (pin "14") (pinfunction "VCC_14") (pintype "power_in"))
      (node (ref "IC5") (pin "11") (pinfunction "1_11") (pintype "input"))
      (node (ref "IC5") (pin "12") (pinfunction "2_12") (pintype "input"))
      (node (ref "IC5") (pin "13") (pinfunction "3_13") (pintype "input"))
      (node (ref "IC5") (pin "16") (pinfunction "VCC_16") (pintype "power_in"))
      (node (ref "IC6") (pin "11") (pinfunction "I6_11") (pintype "input"))
      (node (ref "IC6") (pin "12") (pinfunction "I7_12") (pintype "input"))
      (node (ref "IC6") (pin "14") (pinfunction "VCC_14") (pintype "power_in"))
      (node (ref "IC6") (pin "6") (pinfunction "I5_6") (pintype "input"))
      (node (ref "IC7") (pin "14") (pinfunction "VCC_14") (pintype "power_in"))
      (node (ref "IC8") (pin "32") (pinfunction "VCC_32") (pintype "power_in"))
      (node (ref "IC9") (pin "32") (pinfunction "VCC_32") (pintype "power_in"))
      (node (ref "QG1") (pin "8") (pinfunction "VCC_8") (pintype "power_in"))
      (node (ref "R1") (pin "1") (pinfunction "1_1") (pintype "passive"))
      (node (ref "R2") (pin "1") (pinfunction "1_1") (pintype "passive"))
      (node (ref "R3") (pin "1") (pinfunction "1_1") (pintype "passive"))
      (node (ref "R4") (pin "1") (pinfunction "1_1") (pintype "passive"))
      (node (ref "R8") (pin "1") (pinfunction "1_1") (pintype "passive"))
      (node (ref "R9") (pin "1") (pinfunction "1_1") (pintype "passive"))
      (node (ref "S1") (pin "3") (pinfunction "P_3") (pintype "passive"))
      (node (ref "S1") (pin "4") (pinfunction "P1_4") (pintype "passive"))
      (node (ref "S2") (pin "3") (pinfunction "P_3") (pintype "passive"))
      (node (ref "S2") (pin "4") (pinfunction "P1_4") (pintype "passive"))
      (node (ref "SV1") (pin "2") (pinfunction "2_2") (pintype "passive"))
      (node (ref "X1") (pin "B1") (pinfunction "B_B1") (pintype "passive"))
      (node (ref "X1") (pin "B2") (pinfunction "B_B2") (pintype "passive"))
      (node (ref "X1") (pin "B3") (pinfunction "B_B3") (pintype "passive"))
    )
    (net (code "3") (name "68681_XTAL1") (class "Default")
      (node (ref "C30") (pin "1") (pinfunction "1_1") (pintype "passive"))
      (node (ref "IC14") (pin "36") (pinfunction "X1/CLK_36") (pintype "input"))
      (node (ref "Q1") (pin "2") (pinfunction "2_2") (pintype "passive"))
    )
    (net (code "4") (name "68681_XTAL2") (class "Default")
      (node (ref "C31") (pin "2") (pinfunction "2_2") (pintype "passive"))
      (node (ref "IC14") (pin "37") (pinfunction "X2_37") (pintype "output"))
      (node (ref "Q1") (pin "1") (pinfunction "1_1") (pintype "passive"))
    )
    (net (code "5") (name "A1") (class "Default")
      (node (ref "IC1") (pin "32") (pinfunction "A1_32") (pintype "output"))
      (node (ref "IC10") (pin "12") (pinfunction "A0_12") (pintype "input"))
      (node (ref "IC11") (pin "12") (pinfunction "A0_12") (pintype "input"))
      (node (ref "IC12") (pin "12") (pinfunction "A0_12") (pintype "input"))
      (node (ref "IC13") (pin "12") (pinfunction "A0_12") (pintype "input"))
      (node (ref "IC14") (pin "2") (pinfunction "A1_2") (pintype "input"))
      (node (ref "IC15") (pin "10") (pinfunction "A0_10") (pintype "input"))
      (node (ref "IC8") (pin "12") (pinfunction "A0_12") (pintype "input"))
      (node (ref "IC9") (pin "12") (pinfunction "A0_12") (pintype "input"))
      (node (ref "X1") (pin "A2") (pinfunction "B_A2") (pintype "passive"))
    )
    (net (code "6") (name "A2") (class "Default")
      (node (ref "IC1") (pin "33") (pinfunction "A2_33") (pintype "output"))
      (node (ref "IC10") (pin "11") (pinfunction "A1_11") (pintype "input"))
      (node (ref "IC11") (pin "11") (pinfunction "A1_11") (pintype "input"))
      (node (ref "IC12") (pin "11") (pinfunction "A1_11") (pintype "input"))
      (node (ref "IC13") (pin "11") (pinfunction "A1_11") (pintype "input"))
      (node (ref "IC14") (pin "4") (pinfunction "A2_4") (pintype "input"))
      (node (ref "IC15") (pin "9") (pinfunction "A1_9") (pintype "input"))
      (node (ref "IC8") (pin "11") (pinfunction "A1_11") (pintype "input"))
      (node (ref "IC9") (pin "11") (pinfunction "A1_11") (pintype "input"))
      (node (ref "X1") (pin "A3") (pinfunction "B_A3") (pintype "passive"))
    )
    (net (code "7") (name "A3") (class "Default")
      (node (ref "IC1") (pin "34") (pinfunction "A3_34") (pintype "output"))
      (node (ref "IC10") (pin "10") (pinfunction "A2_10") (pintype "input"))
      (node (ref "IC11") (pin "10") (pinfunction "A2_10") (pintype "input"))
      (node (ref "IC12") (pin "10") (pinfunction "A2_10") (pintype "input"))
      (node (ref "IC13") (pin "10") (pinfunction "A2_10") (pintype "input"))
      (node (ref "IC14") (pin "6") (pinfunction "A3_6") (pintype "input"))
      (node (ref "IC15") (pin "8") (pinfunction "A2_8") (pintype "input"))
      (node (ref "IC8") (pin "10") (pinfunction "A2_10") (pintype "input"))
      (node (ref "IC9") (pin "10") (pinfunction "A2_10") (pintype "input"))
      (node (ref "X1") (pin "A4") (pinfunction "B_A4") (pintype "passive"))
    )
    (net (code "8") (name "A4") (class "Default")
      (node (ref "IC1") (pin "35") (pinfunction "A4_35") (pintype "output"))
      (node (ref "IC10") (pin "9") (pinfunction "A3_9") (pintype "input"))
      (node (ref "IC11") (pin "9") (pinfunction "A3_9") (pintype "input"))
      (node (ref "IC12") (pin "9") (pinfunction "A3_9") (pintype "input"))
      (node (ref "IC13") (pin "9") (pinfunction "A3_9") (pintype "input"))
      (node (ref "IC14") (pin "7") (pinfunction "A4_7") (pintype "input"))
      (node (ref "IC15") (pin "7") (pinfunction "A3_7") (pintype "input"))
      (node (ref "IC8") (pin "9") (pinfunction "A3_9") (pintype "input"))
      (node (ref "IC9") (pin "9") (pinfunction "A3_9") (pintype "input"))
      (node (ref "X1") (pin "A5") (pinfunction "B_A5") (pintype "passive"))
    )
    (net (code "9") (name "A5") (class "Default")
      (node (ref "IC1") (pin "36") (pinfunction "A5_36") (pintype "output"))
      (node (ref "IC10") (pin "8") (pinfunction "A4_8") (pintype "input"))
      (node (ref "IC11") (pin "8") (pinfunction "A4_8") (pintype "input"))
      (node (ref "IC12") (pin "8") (pinfunction "A4_8") (pintype "input"))
      (node (ref "IC13") (pin "8") (pinfunction "A4_8") (pintype "input"))
      (node (ref "IC15") (pin "6") (pinfunction "A4_6") (pintype "input"))
      (node (ref "IC8") (pin "8") (pinfunction "A4_8") (pintype "input"))
      (node (ref "IC9") (pin "8") (pinfunction "A4_8") (pintype "input"))
      (node (ref "X1") (pin "A6") (pinfunction "B_A6") (pintype "passive"))
    )
    (net (code "10") (name "A6") (class "Default")
      (node (ref "IC1") (pin "37") (pinfunction "A6_37") (pintype "output"))
      (node (ref "IC10") (pin "7") (pinfunction "A5_7") (pintype "input"))
      (node (ref "IC11") (pin "7") (pinfunction "A5_7") (pintype "input"))
      (node (ref "IC12") (pin "7") (pinfunction "A5_7") (pintype "input"))
      (node (ref "IC13") (pin "7") (pinfunction "A5_7") (pintype "input"))
      (node (ref "IC15") (pin "5") (pinfunction "A5_5") (pintype "input"))
      (node (ref "IC8") (pin "7") (pinfunction "A5_7") (pintype "input"))
      (node (ref "IC9") (pin "7") (pinfunction "A5_7") (pintype "input"))
      (node (ref "X1") (pin "A7") (pinfunction "B_A7") (pintype "passive"))
    )
    (net (code "11") (name "A7") (class "Default")
      (node (ref "IC1") (pin "38") (pinfunction "A7_38") (pintype "output"))
      (node (ref "IC10") (pin "6") (pinfunction "A6_6") (pintype "input"))
      (node (ref "IC11") (pin "6") (pinfunction "A6_6") (pintype "input"))
      (node (ref "IC12") (pin "6") (pinfunction "A6_6") (pintype "input"))
      (node (ref "IC13") (pin "6") (pinfunction "A6_6") (pintype "input"))
      (node (ref "IC15") (pin "4") (pinfunction "A6_4") (pintype "input"))
      (node (ref "IC8") (pin "6") (pinfunction "A6_6") (pintype "input"))
      (node (ref "IC9") (pin "6") (pinfunction "A6_6") (pintype "input"))
      (node (ref "X1") (pin "A8") (pinfunction "B_A8") (pintype "passive"))
    )
    (net (code "12") (name "A8") (class "Default")
      (node (ref "IC1") (pin "39") (pinfunction "A8_39") (pintype "output"))
      (node (ref "IC10") (pin "5") (pinfunction "A7_5") (pintype "input"))
      (node (ref "IC11") (pin "5") (pinfunction "A7_5") (pintype "input"))
      (node (ref "IC12") (pin "5") (pinfunction "A7_5") (pintype "input"))
      (node (ref "IC13") (pin "5") (pinfunction "A7_5") (pintype "input"))
      (node (ref "IC15") (pin "3") (pinfunction "A7_3") (pintype "input"))
      (node (ref "IC8") (pin "5") (pinfunction "A7_5") (pintype "input"))
      (node (ref "IC9") (pin "5") (pinfunction "A7_5") (pintype "input"))
      (node (ref "X1") (pin "A9") (pinfunction "B_A9") (pintype "passive"))
    )
    (net (code "13") (name "A9") (class "Default")
      (node (ref "IC1") (pin "40") (pinfunction "A9_40") (pintype "output"))
      (node (ref "IC10") (pin "27") (pinfunction "A8_27") (pintype "input"))
      (node (ref "IC11") (pin "27") (pinfunction "A8_27") (pintype "input"))
      (node (ref "IC12") (pin "27") (pinfunction "A8_27") (pintype "input"))
      (node (ref "IC13") (pin "27") (pinfunction "A8_27") (pintype "input"))
      (node (ref "IC15") (pin "25") (pinfunction "A8_25") (pintype "input"))
      (node (ref "IC8") (pin "27") (pinfunction "A8_27") (pintype "input"))
      (node (ref "IC9") (pin "27") (pinfunction "A8_27") (pintype "input"))
      (node (ref "X1") (pin "A10") (pinfunction "B_A10") (pintype "passive"))
    )
    (net (code "14") (name "A10") (class "Default")
      (node (ref "IC1") (pin "41") (pinfunction "A10_41") (pintype "output"))
      (node (ref "IC10") (pin "26") (pinfunction "A9_26") (pintype "input"))
      (node (ref "IC11") (pin "26") (pinfunction "A9_26") (pintype "input"))
      (node (ref "IC12") (pin "26") (pinfunction "A9_26") (pintype "input"))
      (node (ref "IC13") (pin "26") (pinfunction "A9_26") (pintype "input"))
      (node (ref "IC15") (pin "24") (pinfunction "A9_24") (pintype "input"))
      (node (ref "IC8") (pin "26") (pinfunction "A9_26") (pintype "input"))
      (node (ref "IC9") (pin "26") (pinfunction "A9_26") (pintype "input"))
      (node (ref "X1") (pin "A11") (pinfunction "B_A11") (pintype "passive"))
    )
    (net (code "15") (name "A11") (class "Default")
      (node (ref "IC1") (pin "42") (pinfunction "A11_42") (pintype "output"))
      (node (ref "IC10") (pin "23") (pinfunction "A10_23") (pintype "input"))
      (node (ref "IC11") (pin "23") (pinfunction "A10_23") (pintype "input"))
      (node (ref "IC12") (pin "23") (pinfunction "A10_23") (pintype "input"))
      (node (ref "IC13") (pin "23") (pinfunction "A10_23") (pintype "input"))
      (node (ref "IC15") (pin "21") (pinfunction "A10_21") (pintype "input"))
      (node (ref "IC8") (pin "23") (pinfunction "A10_23") (pintype "input"))
      (node (ref "IC9") (pin "23") (pinfunction "A10_23") (pintype "input"))
      (node (ref "X1") (pin "A12") (pinfunction "B_A12") (pintype "passive"))
    )
    (net (code "16") (name "A12") (class "Default")
      (node (ref "IC1") (pin "43") (pinfunction "A12_43") (pintype "output"))
      (node (ref "IC10") (pin "25") (pinfunction "A11_25") (pintype "input"))
      (node (ref "IC11") (pin "25") (pinfunction "A11_25") (pintype "input"))
      (node (ref "IC12") (pin "25") (pinfunction "A11_25") (pintype "input"))
      (node (ref "IC13") (pin "25") (pinfunction "A11_25") (pintype "input"))
      (node (ref "IC15") (pin "23") (pinfunction "A11_23") (pintype "input"))
      (node (ref "IC8") (pin "25") (pinfunction "A11_25") (pintype "input"))
      (node (ref "IC9") (pin "25") (pinfunction "A11_25") (pintype "input"))
      (node (ref "X1") (pin "A13") (pinfunction "B_A13") (pintype "passive"))
    )
    (net (code "17") (name "A13") (class "Default")
      (node (ref "IC1") (pin "44") (pinfunction "A13_44") (pintype "output"))
      (node (ref "IC10") (pin "4") (pinfunction "A12_4") (pintype "input"))
      (node (ref "IC11") (pin "4") (pinfunction "A12_4") (pintype "input"))
      (node (ref "IC12") (pin "4") (pinfunction "A12_4") (pintype "input"))
      (node (ref "IC13") (pin "4") (pinfunction "A12_4") (pintype "input"))
      (node (ref "IC15") (pin "2") (pinfunction "A12_2") (pintype "input"))
      (node (ref "IC8") (pin "4") (pinfunction "A12_4") (pintype "input"))
      (node (ref "IC9") (pin "4") (pinfunction "A12_4") (pintype "input"))
      (node (ref "X1") (pin "A14") (pinfunction "B_A14") (pintype "passive"))
    )
    (net (code "18") (name "A14") (class "Default")
      (node (ref "IC1") (pin "45") (pinfunction "A14_45") (pintype "output"))
      (node (ref "IC10") (pin "28") (pinfunction "A13_28") (pintype "input"))
      (node (ref "IC11") (pin "28") (pinfunction "A13_28") (pintype "input"))
      (node (ref "IC12") (pin "28") (pinfunction "A13_28") (pintype "input"))
      (node (ref "IC13") (pin "28") (pinfunction "A13_28") (pintype "input"))
      (node (ref "IC15") (pin "26") (pinfunction "A13_26") (pintype "input"))
      (node (ref "IC8") (pin "28") (pinfunction "A13_28") (pintype "input"))
      (node (ref "IC9") (pin "28") (pinfunction "A13_28") (pintype "input"))
      (node (ref "X1") (pin "A15") (pinfunction "B_A15") (pintype "passive"))
    )
    (net (code "19") (name "A15") (class "Default")
      (node (ref "IC1") (pin "46") (pinfunction "A15_46") (pintype "output"))
      (node (ref "IC10") (pin "3") (pinfunction "A14_3") (pintype "input"))
      (node (ref "IC11") (pin "3") (pinfunction "A14_3") (pintype "input"))
      (node (ref "IC12") (pin "29") (pinfunction "A14_29") (pintype "input"))
      (node (ref "IC13") (pin "29") (pinfunction "A14_29") (pintype "input"))
      (node (ref "IC15") (pin "1") (pinfunction "A14_1") (pintype "input"))
      (node (ref "IC8") (pin "3") (pinfunction "A14_3") (pintype "input"))
      (node (ref "IC9") (pin "3") (pinfunction "A14_3") (pintype "input"))
      (node (ref "X1") (pin "A16") (pinfunction "B_A16") (pintype "passive"))
    )
    (net (code "20") (name "A16") (class "Default")
      (node (ref "IC1") (pin "47") (pinfunction "A16_47") (pintype "output"))
      (node (ref "IC10") (pin "31") (pinfunction "A15_31") (pintype "input"))
      (node (ref "IC11") (pin "31") (pinfunction "A15_31") (pintype "input"))
      (node (ref "IC12") (pin "3") (pinfunction "A15_3") (pintype "input"))
      (node (ref "IC13") (pin "3") (pinfunction "A15_3") (pintype "input"))
      (node (ref "IC4") (pin "4") (pinfunction "I3_4") (pintype "input"))
      (node (ref "IC8") (pin "31") (pinfunction "A15_31") (pintype "input"))
      (node (ref "IC9") (pin "31") (pinfunction "A15_31") (pintype "input"))
      (node (ref "X1") (pin "A17") (pinfunction "B_A17") (pintype "passive"))
    )
    (net (code "21") (name "A17") (class "Default")
      (node (ref "IC1") (pin "48") (pinfunction "A17_48") (pintype "output"))
      (node (ref "IC10") (pin "2") (pinfunction "A16_2") (pintype "input"))
      (node (ref "IC11") (pin "2") (pinfunction "A16_2") (pintype "input"))
      (node (ref "IC12") (pin "2") (pinfunction "A16_2") (pintype "input"))
      (node (ref "IC13") (pin "2") (pinfunction "A16_2") (pintype "input"))
      (node (ref "IC4") (pin "5") (pinfunction "I4_5") (pintype "input"))
      (node (ref "IC8") (pin "2") (pinfunction "A16_2") (pintype "input"))
      (node (ref "IC9") (pin "2") (pinfunction "A16_2") (pintype "input"))
      (node (ref "X1") (pin "A18") (pinfunction "B_A18") (pintype "passive"))
    )
    (net (code "22") (name "A18") (class "Default")
      (node (ref "IC1") (pin "49") (pinfunction "A18_49") (pintype "output"))
      (node (ref "IC12") (pin "30") (pinfunction "A17_30") (pintype "input"))
      (node (ref "IC13") (pin "30") (pinfunction "A17_30") (pintype "input"))
      (node (ref "IC2") (pin "11") (pinfunction "I_11") (pintype "input"))
      (node (ref "IC4") (pin "6") (pinfunction "I5_6") (pintype "input"))
      (node (ref "X1") (pin "A19") (pinfunction "B_A19") (pintype "passive"))
    )
    (net (code "23") (name "A19") (class "Default")
      (node (ref "IC1") (pin "50") (pinfunction "A19_50") (pintype "output"))
      (node (ref "IC12") (pin "1") (pinfunction "A18_1") (pintype "input"))
      (node (ref "IC13") (pin "1") (pinfunction "A18_1") (pintype "input"))
      (node (ref "IC17") (pin "5") (pinfunction "I1_5") (pintype "input"))
      (node (ref "IC2") (pin "5") (pinfunction "I_5") (pintype "input"))
      (node (ref "IC4") (pin "11") (pinfunction "I6_11") (pintype "input"))
      (node (ref "X1") (pin "A20") (pinfunction "B_A20") (pintype "passive"))
    )
    (net (code "24") (name "A20") (class "Default")
      (node (ref "IC1") (pin "51") (pinfunction "A20_51") (pintype "output"))
      (node (ref "IC3") (pin "23") (pinfunction "A_23") (pintype "input"))
      (node (ref "X1") (pin "A21") (pinfunction "B_A21") (pintype "passive"))
    )
    (net (code "25") (name "A21") (class "Default")
      (node (ref "IC1") (pin "53") (pinfunction "A21_53") (pintype "output"))
      (node (ref "IC3") (pin "22") (pinfunction "B_22") (pintype "input"))
      (node (ref "X1") (pin "A22") (pinfunction "B_A22") (pintype "passive"))
    )
    (net (code "26") (name "A22") (class "Default")
      (node (ref "IC1") (pin "54") (pinfunction "A22_54") (pintype "output"))
      (node (ref "IC3") (pin "21") (pinfunction "C_21") (pintype "input"))
      (node (ref "X1") (pin "A23") (pinfunction "B_A23") (pintype "passive"))
    )
    (net (code "27") (name "A23") (class "Default")
      (node (ref "IC1") (pin "55") (pinfunction "A23_55") (pintype "output"))
      (node (ref "IC3") (pin "20") (pinfunction "D_20") (pintype "input"))
      (node (ref "X1") (pin "A24") (pinfunction "B_A24") (pintype "passive"))
    )
    (net (code "28") (name "CLK") (class "Default")
      (node (ref "IC1") (pin "15") (pinfunction "CLK_15") (pintype "input"))
      (node (ref "QG1") (pin "5") (pinfunction "OUT_5") (pintype "output"))
      (node (ref "X1") (pin "B26") (pinfunction "B_B26") (pintype "passive"))
    )
    (net (code "29") (name "D0") (class "Default")
      (node (ref "IC1") (pin "5") (pinfunction "D0_5") (pintype "bidirectional"))
      (node (ref "IC10") (pin "13") (pinfunction "D0_13") (pintype "bidirectional"))
      (node (ref "IC11") (pin "13") (pinfunction "D0_13") (pintype "bidirectional"))
      (node (ref "IC13") (pin "13") (pinfunction "DQ0_13") (pintype "bidirectional"))
      (node (ref "IC14") (pin "28") (pinfunction "D0_28") (pintype "bidirectional"))
      (node (ref "IC15") (pin "11") (pinfunction "DQ0_11") (pintype "bidirectional"))
      (node (ref "X1") (pin "C1") (pinfunction "B_C1") (pintype "passive"))
    )
    (net (code "30") (name "D1") (class "Default")
      (node (ref "IC1") (pin "4") (pinfunction "D1_4") (pintype "bidirectional"))
      (node (ref "IC10") (pin "14") (pinfunction "D1_14") (pintype "bidirectional"))
      (node (ref "IC11") (pin "14") (pinfunction "D1_14") (pintype "bidirectional"))
      (node (ref "IC13") (pin "14") (pinfunction "DQ1_14") (pintype "bidirectional"))
      (node (ref "IC14") (pin "18") (pinfunction "D1_18") (pintype "bidirectional"))
      (node (ref "IC15") (pin "12") (pinfunction "DQ1_12") (pintype "bidirectional"))
      (node (ref "X1") (pin "C2") (pinfunction "B_C2") (pintype "passive"))
    )
    (net (code "31") (name "D2") (class "Default")
      (node (ref "IC1") (pin "3") (pinfunction "D2_3") (pintype "bidirectional"))
      (node (ref "IC10") (pin "15") (pinfunction "D2_15") (pintype "bidirectional"))
      (node (ref "IC11") (pin "15") (pinfunction "D2_15") (pintype "bidirectional"))
      (node (ref "IC13") (pin "15") (pinfunction "DQ2_15") (pintype "bidirectional"))
      (node (ref "IC14") (pin "27") (pinfunction "D2_27") (pintype "bidirectional"))
      (node (ref "IC15") (pin "13") (pinfunction "DQ2_13") (pintype "bidirectional"))
      (node (ref "X1") (pin "C3") (pinfunction "B_C3") (pintype "passive"))
    )
    (net (code "32") (name "D3") (class "Default")
      (node (ref "IC1") (pin "2") (pinfunction "D3_2") (pintype "bidirectional"))
      (node (ref "IC10") (pin "17") (pinfunction "D3_17") (pintype "bidirectional"))
      (node (ref "IC11") (pin "17") (pinfunction "D3_17") (pintype "bidirectional"))
      (node (ref "IC13") (pin "17") (pinfunction "DQ3_17") (pintype "bidirectional"))
      (node (ref "IC14") (pin "19") (pinfunction "D3_19") (pintype "bidirectional"))
      (node (ref "IC15") (pin "15") (pinfunction "DQ3_15") (pintype "bidirectional"))
      (node (ref "X1") (pin "C4") (pinfunction "B_C4") (pintype "passive"))
    )
    (net (code "33") (name "D4") (class "Default")
      (node (ref "IC1") (pin "1") (pinfunction "D4_1") (pintype "bidirectional"))
      (node (ref "IC10") (pin "18") (pinfunction "D4_18") (pintype "bidirectional"))
      (node (ref "IC11") (pin "18") (pinfunction "D4_18") (pintype "bidirectional"))
      (node (ref "IC13") (pin "18") (pinfunction "DQ4_18") (pintype "bidirectional"))
      (node (ref "IC14") (pin "26") (pinfunction "D4_26") (pintype "bidirectional"))
      (node (ref "IC15") (pin "16") (pinfunction "DQ4_16") (pintype "bidirectional"))
      (node (ref "X1") (pin "C5") (pinfunction "B_C5") (pintype "passive"))
    )
    (net (code "34") (name "D5") (class "Default")
      (node (ref "IC1") (pin "68") (pinfunction "D5_68") (pintype "bidirectional"))
      (node (ref "IC10") (pin "19") (pinfunction "D5_19") (pintype "bidirectional"))
      (node (ref "IC11") (pin "19") (pinfunction "D5_19") (pintype "bidirectional"))
      (node (ref "IC13") (pin "19") (pinfunction "DQ5_19") (pintype "bidirectional"))
      (node (ref "IC14") (pin "20") (pinfunction "D5_20") (pintype "bidirectional"))
      (node (ref "IC15") (pin "17") (pinfunction "DQ5_17") (pintype "bidirectional"))
      (node (ref "X1") (pin "C6") (pinfunction "B_C6") (pintype "passive"))
    )
    (net (code "35") (name "D6") (class "Default")
      (node (ref "IC1") (pin "67") (pinfunction "D6_67") (pintype "bidirectional"))
      (node (ref "IC10") (pin "20") (pinfunction "D6_20") (pintype "bidirectional"))
      (node (ref "IC11") (pin "20") (pinfunction "D6_20") (pintype "bidirectional"))
      (node (ref "IC13") (pin "20") (pinfunction "DQ6_20") (pintype "bidirectional"))
      (node (ref "IC14") (pin "25") (pinfunction "D6_25") (pintype "bidirectional"))
      (node (ref "IC15") (pin "18") (pinfunction "DQ6_18") (pintype "bidirectional"))
      (node (ref "X1") (pin "C7") (pinfunction "B_C7") (pintype "passive"))
    )
    (net (code "36") (name "D7") (class "Default")
      (node (ref "IC1") (pin "66") (pinfunction "D7_66") (pintype "bidirectional"))
      (node (ref "IC10") (pin "21") (pinfunction "D7_21") (pintype "bidirectional"))
      (node (ref "IC11") (pin "21") (pinfunction "D7_21") (pintype "bidirectional"))
      (node (ref "IC13") (pin "21") (pinfunction "DQ7_21") (pintype "bidirectional"))
      (node (ref "IC14") (pin "21") (pinfunction "D7_21") (pintype "bidirectional"))
      (node (ref "IC15") (pin "19") (pinfunction "DQ7_19") (pintype "bidirectional"))
      (node (ref "X1") (pin "C8") (pinfunction "B_C8") (pintype "passive"))
    )
    (net (code "37") (name "D8") (class "Default")
      (node (ref "IC1") (pin "65") (pinfunction "D8_65") (pintype "bidirectional"))
      (node (ref "IC12") (pin "13") (pinfunction "DQ0_13") (pintype "bidirectional"))
      (node (ref "IC8") (pin "13") (pinfunction "D0_13") (pintype "bidirectional"))
      (node (ref "IC9") (pin "13") (pinfunction "D0_13") (pintype "bidirectional"))
      (node (ref "X1") (pin "C9") (pinfunction "B_C9") (pintype "passive"))
    )
    (net (code "38") (name "D9") (class "Default")
      (node (ref "IC1") (pin "64") (pinfunction "D9_64") (pintype "bidirectional"))
      (node (ref "IC12") (pin "14") (pinfunction "DQ1_14") (pintype "bidirectional"))
      (node (ref "IC8") (pin "14") (pinfunction "D1_14") (pintype "bidirectional"))
      (node (ref "IC9") (pin "14") (pinfunction "D1_14") (pintype "bidirectional"))
      (node (ref "X1") (pin "C10") (pinfunction "B_C10") (pintype "passive"))
    )
    (net (code "39") (name "D10") (class "Default")
      (node (ref "IC1") (pin "63") (pinfunction "D10_63") (pintype "bidirectional"))
      (node (ref "IC12") (pin "15") (pinfunction "DQ2_15") (pintype "bidirectional"))
      (node (ref "IC8") (pin "15") (pinfunction "D2_15") (pintype "bidirectional"))
      (node (ref "IC9") (pin "15") (pinfunction "D2_15") (pintype "bidirectional"))
      (node (ref "X1") (pin "C11") (pinfunction "B_C11") (pintype "passive"))
    )
    (net (code "40") (name "D11") (class "Default")
      (node (ref "IC1") (pin "62") (pinfunction "D11_62") (pintype "bidirectional"))
      (node (ref "IC12") (pin "17") (pinfunction "DQ3_17") (pintype "bidirectional"))
      (node (ref "IC8") (pin "17") (pinfunction "D3_17") (pintype "bidirectional"))
      (node (ref "IC9") (pin "17") (pinfunction "D3_17") (pintype "bidirectional"))
      (node (ref "X1") (pin "C12") (pinfunction "B_C12") (pintype "passive"))
    )
    (net (code "41") (name "D12") (class "Default")
      (node (ref "IC1") (pin "61") (pinfunction "D12_61") (pintype "bidirectional"))
      (node (ref "IC12") (pin "18") (pinfunction "DQ4_18") (pintype "bidirectional"))
      (node (ref "IC8") (pin "18") (pinfunction "D4_18") (pintype "bidirectional"))
      (node (ref "IC9") (pin "18") (pinfunction "D4_18") (pintype "bidirectional"))
      (node (ref "X1") (pin "C13") (pinfunction "B_C13") (pintype "passive"))
    )
    (net (code "42") (name "D13") (class "Default")
      (node (ref "IC1") (pin "60") (pinfunction "D13_60") (pintype "bidirectional"))
      (node (ref "IC12") (pin "19") (pinfunction "DQ5_19") (pintype "bidirectional"))
      (node (ref "IC8") (pin "19") (pinfunction "D5_19") (pintype "bidirectional"))
      (node (ref "IC9") (pin "19") (pinfunction "D5_19") (pintype "bidirectional"))
      (node (ref "X1") (pin "C14") (pinfunction "B_C14") (pintype "passive"))
    )
    (net (code "43") (name "D14") (class "Default")
      (node (ref "IC1") (pin "59") (pinfunction "D14_59") (pintype "bidirectional"))
      (node (ref "IC12") (pin "20") (pinfunction "DQ6_20") (pintype "bidirectional"))
      (node (ref "IC8") (pin "20") (pinfunction "D6_20") (pintype "bidirectional"))
      (node (ref "IC9") (pin "20") (pinfunction "D6_20") (pintype "bidirectional"))
      (node (ref "X1") (pin "C15") (pinfunction "B_C15") (pintype "passive"))
    )
    (net (code "44") (name "D15") (class "Default")
      (node (ref "IC1") (pin "58") (pinfunction "D15_58") (pintype "bidirectional"))
      (node (ref "IC12") (pin "21") (pinfunction "DQ7_21") (pintype "bidirectional"))
      (node (ref "IC8") (pin "21") (pinfunction "D7_21") (pintype "bidirectional"))
      (node (ref "IC9") (pin "21") (pinfunction "D7_21") (pintype "bidirectional"))
      (node (ref "X1") (pin "C16") (pinfunction "B_C16") (pintype "passive"))
    )
    (net (code "45") (name "DTACK") (class "Default")
      (node (ref "IC2") (pin "9") (pinfunction "I_9") (pintype "input"))
      (node (ref "IC6") (pin "8") (pinfunction "O_8") (pintype "output"))
    )
    (net (code "46") (name "FC0") (class "Default")
      (node (ref "IC1") (pin "30") (pinfunction "FC0_30") (pintype "output"))
      (node (ref "IC4") (pin "1") (pinfunction "I0_1") (pintype "input"))
      (node (ref "X1") (pin "B6") (pinfunction "B_B6") (pintype "passive"))
    )
    (net (code "47") (name "FC1") (class "Default")
      (node (ref "IC1") (pin "29") (pinfunction "FC1_29") (pintype "output"))
      (node (ref "IC4") (pin "2") (pinfunction "I1_2") (pintype "input"))
      (node (ref "X1") (pin "B7") (pinfunction "B_B7") (pintype "passive"))
    )
    (net (code "48") (name "FC2") (class "Default")
      (node (ref "IC1") (pin "28") (pinfunction "FC2_28") (pintype "output"))
      (node (ref "IC4") (pin "3") (pinfunction "I2_3") (pintype "input"))
      (node (ref "X1") (pin "B8") (pinfunction "B_B8") (pintype "passive"))
    )
    (net (code "49") (name "GND") (class "Default")
      (node (ref "C1") (pin "2") (pinfunction "2_2") (pintype "passive"))
      (node (ref "C10") (pin "2") (pinfunction "2_2") (pintype "passive"))
      (node (ref "C11") (pin "-") (pinfunction "-_-") (pintype "passive"))
      (node (ref "C12") (pin "2") (pinfunction "2_2") (pintype "passive"))
      (node (ref "C13") (pin "2") (pinfunction "2_2") (pintype "passive"))
      (node (ref "C14") (pin "2") (pinfunction "2_2") (pintype "passive"))
      (node (ref "C15") (pin "2") (pinfunction "2_2") (pintype "passive"))
      (node (ref "C16") (pin "2") (pinfunction "2_2") (pintype "passive"))
      (node (ref "C17") (pin "2") (pinfunction "2_2") (pintype "passive"))
      (node (ref "C18") (pin "2") (pinfunction "2_2") (pintype "passive"))
      (node (ref "C19") (pin "-") (pinfunction "-_-") (pintype "passive"))
      (node (ref "C2") (pin "2") (pinfunction "2_2") (pintype "passive"))
      (node (ref "C20") (pin "2") (pinfunction "2_2") (pintype "passive"))
      (node (ref "C21") (pin "2") (pinfunction "2_2") (pintype "passive"))
      (node (ref "C22") (pin "2") (pinfunction "2_2") (pintype "passive"))
      (node (ref "C23") (pin "2") (pinfunction "2_2") (pintype "passive"))
      (node (ref "C24") (pin "-") (pinfunction "-_-") (pintype "passive"))
      (node (ref "C25") (pin "2") (pinfunction "2_2") (pintype "passive"))
      (node (ref "C26") (pin "2") (pinfunction "2_2") (pintype "passive"))
      (node (ref "C27") (pin "-") (pinfunction "-_-") (pintype "passive"))
      (node (ref "C28") (pin "2") (pinfunction "2_2") (pintype "passive"))
      (node (ref "C29") (pin "2") (pinfunction "2_2") (pintype "passive"))
      (node (ref "C3") (pin "2") (pinfunction "2_2") (pintype "passive"))
      (node (ref "C30") (pin "2") (pinfunction "2_2") (pintype "passive"))
      (node (ref "C31") (pin "1") (pinfunction "1_1") (pintype "passive"))
      (node (ref "C32") (pin "-") (pinfunction "-_-") (pintype "passive"))
      (node (ref "C36") (pin "+") (pinfunction "+_+") (pintype "passive"))
      (node (ref "C37") (pin "2") (pinfunction "2_2") (pintype "passive"))
      (node (ref "C38") (pin "2") (pinfunction "2_2") (pintype "passive"))
      (node (ref "C39") (pin "2") (pinfunction "2_2") (pintype "passive"))
      (node (ref "C4") (pin "-") (pinfunction "-_-") (pintype "passive"))
      (node (ref "C40") (pin "-") (pinfunction "-_-") (pintype "passive"))
      (node (ref "C5") (pin "2") (pinfunction "2_2") (pintype "passive"))
      (node (ref "C6") (pin "2") (pinfunction "2_2") (pintype "passive"))
      (node (ref "C7") (pin "2") (pinfunction "2_2") (pintype "passive"))
      (node (ref "C8") (pin "-") (pinfunction "-_-") (pintype "passive"))
      (node (ref "C9") (pin "2") (pinfunction "2_2") (pintype "passive"))
      (node (ref "IC1") (pin "16") (pinfunction "GND_16") (pintype "power_in"))
      (node (ref "IC1") (pin "17") (pinfunction "GND_17") (pintype "power_in"))
      (node (ref "IC1") (pin "56") (pinfunction "GND_56") (pintype "power_in"))
      (node (ref "IC1") (pin "57") (pinfunction "GND_57") (pintype "power_in"))
      (node (ref "IC10") (pin "16") (pinfunction "GND_16") (pintype "power_in"))
      (node (ref "IC11") (pin "16") (pinfunction "GND_16") (pintype "power_in"))
      (node (ref "IC12") (pin "16") (pinfunction "GND_16") (pintype "power_in"))
      (node (ref "IC13") (pin "16") (pinfunction "GND_16") (pintype "power_in"))
      (node (ref "IC14") (pin "22") (pinfunction "GND_22") (pintype "power_in"))
      (node (ref "IC15") (pin "14") (pinfunction "GND_14") (pintype "power_in"))
      (node (ref "IC16") (pin "15") (pinfunction "GND_15") (pintype "power_in"))
      (node (ref "IC17") (pin "7") (pinfunction "GND_7") (pintype "power_in"))
      (node (ref "IC2") (pin "13") (pinfunction "I_13") (pintype "input"))
      (node (ref "IC2") (pin "7") (pinfunction "GND_7") (pintype "power_in"))
      (node (ref "IC3") (pin "12") (pinfunction "GND_12") (pintype "power_in"))
      (node (ref "IC4") (pin "7") (pinfunction "GND_7") (pintype "power_in"))
      (node (ref "IC5") (pin "10") (pinfunction "0_10") (pintype "input"))
      (node (ref "IC5") (pin "5") (pinfunction "EI_5") (pintype "input"))
      (node (ref "IC5") (pin "8") (pinfunction "GND_8") (pintype "power_in"))
      (node (ref "IC6") (pin "7") (pinfunction "GND_7") (pintype "power_in"))
      (node (ref "IC7") (pin "5") (pinfunction "I_5") (pintype "input"))
      (node (ref "IC7") (pin "7") (pinfunction "GND_7") (pintype "power_in"))
      (node (ref "IC8") (pin "16") (pinfunction "GND_16") (pintype "power_in"))
      (node (ref "IC9") (pin "16") (pinfunction "GND_16") (pintype "power_in"))
      (node (ref "LED1") (pin "C") (pinfunction "C_C") (pintype "passive"))
      (node (ref "LED10") (pin "C") (pinfunction "C_C") (pintype "passive"))
      (node (ref "LED4") (pin "C") (pinfunction "C_C") (pintype "passive"))
      (node (ref "LED5") (pin "C") (pinfunction "C_C") (pintype "passive"))
      (node (ref "LED6") (pin "C") (pinfunction "C_C") (pintype "passive"))
      (node (ref "LED7") (pin "C") (pinfunction "C_C") (pintype "passive"))
      (node (ref "LED8") (pin "C") (pinfunction "C_C") (pintype "passive"))
      (node (ref "LED9") (pin "C") (pinfunction "C_C") (pintype "passive"))
      (node (ref "QG1") (pin "4") (pinfunction "GND_4") (pintype "power_in"))
      (node (ref "R12") (pin "2") (pinfunction "2_2") (pintype "passive"))
      (node (ref "R13") (pin "2") (pinfunction "2_2") (pintype "passive"))
      (node (ref "SV1") (pin "1") (pinfunction "1_1") (pintype "passive"))
      (node (ref "X1") (pin "A25") (pinfunction "B_A25") (pintype "passive"))
      (node (ref "X1") (pin "A26") (pinfunction "B_A26") (pintype "passive"))
      (node (ref "X1") (pin "A27") (pinfunction "B_A27") (pintype "passive"))
      (node (ref "X1") (pin "A28") (pinfunction "B_A28") (pintype "passive"))
      (node (ref "X1") (pin "A29") (pinfunction "B_A29") (pintype "passive"))
      (node (ref "X1") (pin "A30") (pinfunction "B_A30") (pintype "passive"))
      (node (ref "X1") (pin "A31") (pinfunction "B_A31") (pintype "passive"))
      (node (ref "X1") (pin "A32") (pinfunction "B_A32") (pintype "passive"))
      (node (ref "X1") (pin "B25") (pinfunction "B_B25") (pintype "passive"))
      (node (ref "X1") (pin "B27") (pinfunction "B_B27") (pintype "passive"))
      (node (ref "X1") (pin "B30") (pinfunction "B_B30") (pintype "passive"))
      (node (ref "X1") (pin "B31") (pinfunction "B_B31") (pintype "passive"))
      (node (ref "X1") (pin "B32") (pinfunction "B_B32") (pintype "passive"))
      (node (ref "X2") (pin "5") (pinfunction "5_5") (pintype "passive"))
      (node (ref "X2") (pin "G1") (pinfunction "G1_G1") (pintype "passive"))
      (node (ref "X2") (pin "G2") (pinfunction "G2_G2") (pintype "passive"))
      (node (ref "X3") (pin "5") (pinfunction "5_5") (pintype "passive"))
      (node (ref "X3") (pin "G1") (pinfunction "G1_G1") (pintype "passive"))
      (node (ref "X3") (pin "G2") (pinfunction "G2_G2") (pintype "passive"))
    )
    (net (code "50") (name "GPIO_OUT0") (class "Default")
      (node (ref "IC14") (pin "32") (pinfunction "OP0_32") (pintype "output"))
      (node (ref "R14") (pin "1") (pinfunction "1_1") (pintype "passive"))
    )
    (net (code "51") (name "GPIO_OUT1") (class "Default")
      (node (ref "IC14") (pin "14") (pinfunction "OP1_14") (pintype "output"))
      (node (ref "R15") (pin "1") (pinfunction "1_1") (pintype "passive"))
    )
    (net (code "52") (name "GPIO_OUT2") (class "Default")
      (node (ref "IC14") (pin "15") (pinfunction "OP3_15") (pintype "output"))
      (node (ref "R16") (pin "1") (pinfunction "1_1") (pintype "passive"))
    )
    (net (code "53") (name "GPIO_OUT3") (class "Default")
      (node (ref "IC14") (pin "30") (pinfunction "OP4_30") (pintype "output"))
      (node (ref "R17") (pin "1") (pinfunction "1_1") (pintype "passive"))
    )
    (net (code "54") (name "GPIO_OUT4") (class "Default")
      (node (ref "IC14") (pin "16") (pinfunction "OP5_16") (pintype "output"))
      (node (ref "R18") (pin "1") (pinfunction "1_1") (pintype "passive"))
    )
    (net (code "55") (name "GPIO_OUT5") (class "Default")
      (node (ref "IC14") (pin "29") (pinfunction "OP6_29") (pintype "output"))
      (node (ref "R19") (pin "1") (pinfunction "1_1") (pintype "passive"))
    )
    (net (code "56") (name "GPIO_OUT6") (class "Default")
      (node (ref "IC14") (pin "17") (pinfunction "OP7_17") (pintype "output"))
      (node (ref "R20") (pin "1") (pinfunction "1_1") (pintype "passive"))
    )
    (net (code "57") (name "NMI_SW") (class "Default")
      (node (ref "C12") (pin "1") (pinfunction "1_1") (pintype "passive"))
      (node (ref "IC7") (pin "13") (pinfunction "I_13") (pintype "input"))
      (node (ref "R10") (pin "1") (pinfunction "1_1") (pintype "passive"))
      (node (ref "R12") (pin "1") (pinfunction "1_1") (pintype "passive"))
    )
    (net (code "58") (name "Net-(IC16A-C1+)") (class "Default")
      (node (ref "C33") (pin "+") (pinfunction "+_+") (pintype "passive"))
      (node (ref "IC16") (pin "1") (pinfunction "C1+_1") (pintype "bidirectional"))
    )
    (net (code "59") (name "Net-(IC16A-C1-)") (class "Default")
      (node (ref "C33") (pin "-") (pinfunction "-_-") (pintype "passive"))
      (node (ref "IC16") (pin "3") (pinfunction "C1-_3") (pintype "bidirectional"))
    )
    (net (code "60") (name "Net-(IC16A-C2+)") (class "Default")
      (node (ref "C34") (pin "+") (pinfunction "+_+") (pintype "passive"))
      (node (ref "IC16") (pin "4") (pinfunction "C2+_4") (pintype "bidirectional"))
    )
    (net (code "61") (name "Net-(IC16A-C2-)") (class "Default")
      (node (ref "C34") (pin "-") (pinfunction "-_-") (pintype "passive"))
      (node (ref "IC16") (pin "5") (pinfunction "C2-_5") (pintype "bidirectional"))
    )
    (net (code "62") (name "Net-(IC16A-V+)") (class "Default")
      (node (ref "C35") (pin "+") (pinfunction "+_+") (pintype "passive"))
      (node (ref "IC16") (pin "2") (pinfunction "V+_2") (pintype "bidirectional"))
    )
    (net (code "63") (name "Net-(IC16A-V-)") (class "Default")
      (node (ref "C36") (pin "-") (pinfunction "-_-") (pintype "passive"))
      (node (ref "IC16") (pin "6") (pinfunction "V-_6") (pintype "bidirectional"))
    )
    (net (code "64") (name "Net-(LED1-PadA)") (class "Default")
      (node (ref "LED1") (pin "A") (pinfunction "A_A") (pintype "passive"))
      (node (ref "R3") (pin "2") (pinfunction "2_2") (pintype "passive"))
    )
    (net (code "65") (name "Net-(LED2-PadA)") (class "Default")
      (node (ref "LED2") (pin "A") (pinfunction "A_A") (pintype "passive"))
      (node (ref "R1") (pin "2") (pinfunction "2_2") (pintype "passive"))
    )
    (net (code "66") (name "Net-(LED3-PadA)") (class "Default")
      (node (ref "LED3") (pin "A") (pinfunction "A_A") (pintype "passive"))
      (node (ref "R2") (pin "2") (pinfunction "2_2") (pintype "passive"))
    )
    (net (code "67") (name "Net-(LED4-PadA)") (class "Default")
      (node (ref "LED4") (pin "A") (pinfunction "A_A") (pintype "passive"))
      (node (ref "R14") (pin "2") (pinfunction "2_2") (pintype "passive"))
    )
    (net (code "68") (name "Net-(LED5-PadA)") (class "Default")
      (node (ref "LED5") (pin "A") (pinfunction "A_A") (pintype "passive"))
      (node (ref "R15") (pin "2") (pinfunction "2_2") (pintype "passive"))
    )
    (net (code "69") (name "Net-(LED6-PadA)") (class "Default")
      (node (ref "LED6") (pin "A") (pinfunction "A_A") (pintype "passive"))
      (node (ref "R16") (pin "2") (pinfunction "2_2") (pintype "passive"))
    )
    (net (code "70") (name "Net-(LED7-PadA)") (class "Default")
      (node (ref "LED7") (pin "A") (pinfunction "A_A") (pintype "passive"))
      (node (ref "R17") (pin "2") (pinfunction "2_2") (pintype "passive"))
    )
    (net (code "71") (name "Net-(LED8-PadA)") (class "Default")
      (node (ref "LED8") (pin "A") (pinfunction "A_A") (pintype "passive"))
      (node (ref "R18") (pin "2") (pinfunction "2_2") (pintype "passive"))
    )
    (net (code "72") (name "Net-(LED9-PadA)") (class "Default")
      (node (ref "LED9") (pin "A") (pinfunction "A_A") (pintype "passive"))
      (node (ref "R19") (pin "2") (pinfunction "2_2") (pintype "passive"))
    )
    (net (code "73") (name "Net-(LED10-PadA)") (class "Default")
      (node (ref "LED10") (pin "A") (pinfunction "A_A") (pintype "passive"))
      (node (ref "R20") (pin "2") (pinfunction "2_2") (pintype "passive"))
    )
    (net (code "74") (name "Net-(S1-S)") (class "Default")
      (node (ref "R10") (pin "2") (pinfunction "2_2") (pintype "passive"))
      (node (ref "S1") (pin "1") (pinfunction "S_1") (pintype "passive"))
      (node (ref "S1") (pin "2") (pinfunction "S1_2") (pintype "passive"))
    )
    (net (code "75") (name "Net-(S2-S)") (class "Default")
      (node (ref "R11") (pin "2") (pinfunction "2_2") (pintype "passive"))
      (node (ref "S2") (pin "1") (pinfunction "S_1") (pintype "passive"))
      (node (ref "S2") (pin "2") (pinfunction "S1_2") (pintype "passive"))
    )
    (net (code "76") (name "REGION15") (class "Default")
      (node (ref "IC17") (pin "1") (pinfunction "I0_1") (pintype "input"))
      (node (ref "IC17") (pin "4") (pinfunction "I0_4") (pintype "input"))
      (node (ref "IC2") (pin "4") (pinfunction "O_4") (pintype "output"))
    )
    (net (code "77") (name "RESET_SW") (class "Default")
      (node (ref "C13") (pin "1") (pinfunction "1_1") (pintype "passive"))
      (node (ref "IC7") (pin "11") (pinfunction "I_11") (pintype "input"))
      (node (ref "IC7") (pin "9") (pinfunction "I_9") (pintype "input"))
      (node (ref "R11") (pin "1") (pinfunction "1_1") (pintype "passive"))
      (node (ref "R13") (pin "1") (pinfunction "1_1") (pintype "passive"))
    )
    (net (code "78") (name "RS232_0_RX") (class "Default")
      (node (ref "IC16") (pin "14") (pinfunction "T1OUT_14") (pintype "output"))
      (node (ref "X2") (pin "2") (pinfunction "2_2") (pintype "passive"))
    )
    (net (code "79") (name "RS232_0_TX") (class "Default")
      (node (ref "IC16") (pin "13") (pinfunction "R1IN_13") (pintype "input"))
      (node (ref "X2") (pin "3") (pinfunction "3_3") (pintype "passive"))
    )
    (net (code "80") (name "RS232_1_RX") (class "Default")
      (node (ref "IC16") (pin "7") (pinfunction "T2OUT_7") (pintype "output"))
      (node (ref "X3") (pin "2") (pinfunction "2_2") (pintype "passive"))
    )
    (net (code "81") (name "RS232_1_TX") (class "Default")
      (node (ref "IC16") (pin "8") (pinfunction "R2IN_8") (pintype "input"))
      (node (ref "X3") (pin "3") (pinfunction "3_3") (pintype "passive"))
    )
    (net (code "82") (name "R{slash}~{W}") (class "Default")
      (node (ref "IC10") (pin "29") (pinfunction "~{WE}_29") (pintype "input"))
      (node (ref "IC11") (pin "29") (pinfunction "~{WE}_29") (pintype "input"))
      (node (ref "IC12") (pin "31") (pinfunction "~{WE}_31") (pintype "input"))
      (node (ref "IC13") (pin "31") (pinfunction "~{WE}_31") (pintype "input"))
      (node (ref "IC14") (pin "9") (pinfunction "R/~{W}_9") (pintype "input"))
      (node (ref "IC15") (pin "27") (pinfunction "~{WE}_27") (pintype "input"))
      (node (ref "IC8") (pin "29") (pinfunction "~{WE}_29") (pintype "input"))
      (node (ref "IC9") (pin "29") (pinfunction "~{WE}_29") (pintype "input"))
    )
    (net (code "83") (name "R~{W}") (class "Default")
      (node (ref "IC1") (pin "9") (pinfunction "R/W_9") (pintype "output"))
      (node (ref "IC2") (pin "1") (pinfunction "I_1") (pintype "input"))
      (node (ref "X1") (pin "B22") (pinfunction "B_B22") (pintype "passive"))
    )
    (net (code "84") (name "UART0_RX") (class "Default")
      (node (ref "IC14") (pin "35") (pinfunction "RXDA_35") (pintype "input"))
      (node (ref "IC16") (pin "12") (pinfunction "R1OUT_12") (pintype "output"))
    )
    (net (code "85") (name "UART0_TX") (class "Default")
      (node (ref "IC14") (pin "33") (pinfunction "TXDA_33") (pintype "output"))
      (node (ref "IC16") (pin "11") (pinfunction "T1IN_11") (pintype "input"))
    )
    (net (code "86") (name "UART1_RX") (class "Default")
      (node (ref "IC14") (pin "11") (pinfunction "RXDB_11") (pintype "output"))
      (node (ref "IC16") (pin "9") (pinfunction "R2OUT_9") (pintype "output"))
    )
    (net (code "87") (name "UART1_TX") (class "Default")
      (node (ref "IC14") (pin "13") (pinfunction "TXDB_13") (pintype "bidirectional"))
      (node (ref "IC16") (pin "10") (pinfunction "T2IN_10") (pintype "input"))
    )
    (net (code "88") (name "unconnected-(IC1A-E-Pad22)") (class "Default")
      (node (ref "IC1") (pin "22") (pinfunction "E_22") (pintype "output"))
    )
    (net (code "89") (name "unconnected-(IC1A-VMA-Pad21)") (class "Default")
      (node (ref "IC1") (pin "21") (pinfunction "VMA_21") (pintype "output"))
    )
    (net (code "90") (name "unconnected-(IC2F-O-Pad12)") (class "Default")
      (node (ref "IC2") (pin "12") (pinfunction "O_12") (pintype "output"))
    )
    (net (code "91") (name "unconnected-(IC3A-2-Pad3)") (class "Default")
      (node (ref "IC3") (pin "3") (pinfunction "2_3") (pintype "output"))
    )
    (net (code "92") (name "unconnected-(IC3A-3-Pad4)") (class "Default")
      (node (ref "IC3") (pin "4") (pinfunction "3_4") (pintype "output"))
    )
    (net (code "93") (name "unconnected-(IC3A-4-Pad5)") (class "Default")
      (node (ref "IC3") (pin "5") (pinfunction "4_5") (pintype "output"))
    )
    (net (code "94") (name "unconnected-(IC3A-5-Pad6)") (class "Default")
      (node (ref "IC3") (pin "6") (pinfunction "5_6") (pintype "output"))
    )
    (net (code "95") (name "unconnected-(IC3A-6-Pad7)") (class "Default")
      (node (ref "IC3") (pin "7") (pinfunction "6_7") (pintype "output"))
    )
    (net (code "96") (name "unconnected-(IC3A-7-Pad8)") (class "Default")
      (node (ref "IC3") (pin "8") (pinfunction "7_8") (pintype "output"))
    )
    (net (code "97") (name "unconnected-(IC3A-8-Pad9)") (class "Default")
      (node (ref "IC3") (pin "9") (pinfunction "8_9") (pintype "output"))
    )
    (net (code "98") (name "unconnected-(IC3A-9-Pad10)") (class "Default")
      (node (ref "IC3") (pin "10") (pinfunction "9_10") (pintype "output"))
    )
    (net (code "99") (name "unconnected-(IC3A-10-Pad11)") (class "Default")
      (node (ref "IC3") (pin "11") (pinfunction "10_11") (pintype "output"))
    )
    (net (code "100") (name "unconnected-(IC3A-11-Pad13)") (class "Default")
      (node (ref "IC3") (pin "13") (pinfunction "11_13") (pintype "output"))
    )
    (net (code "101") (name "unconnected-(IC3A-12-Pad14)") (class "Default")
      (node (ref "IC3") (pin "14") (pinfunction "12_14") (pintype "output"))
    )
    (net (code "102") (name "unconnected-(IC3A-13-Pad15)") (class "Default")
      (node (ref "IC3") (pin "15") (pinfunction "13_15") (pintype "output"))
    )
    (net (code "103") (name "unconnected-(IC3A-14-Pad16)") (class "Default")
      (node (ref "IC3") (pin "16") (pinfunction "14_16") (pintype "output"))
    )
    (net (code "104") (name "unconnected-(IC5A-EO-Pad15)") (class "Default")
      (node (ref "IC5") (pin "15") (pinfunction "EO_15") (pintype "output"))
    )
    (net (code "105") (name "unconnected-(IC5A-GS-Pad14)") (class "Default")
      (node (ref "IC5") (pin "14") (pinfunction "GS_14") (pintype "output"))
    )
    (net (code "106") (name "unconnected-(IC7D-I-Pad1)") (class "Default")
      (node (ref "IC7") (pin "1") (pinfunction "I_1") (pintype "input"))
    )
    (net (code "107") (name "unconnected-(IC7D-O-Pad2)") (class "Default")
      (node (ref "IC7") (pin "2") (pinfunction "O_2") (pintype "output"))
    )
    (net (code "108") (name "unconnected-(IC7E-I-Pad3)") (class "Default")
      (node (ref "IC7") (pin "3") (pinfunction "I_3") (pintype "input"))
    )
    (net (code "109") (name "unconnected-(IC7E-O-Pad4)") (class "Default")
      (node (ref "IC7") (pin "4") (pinfunction "O_4") (pintype "output"))
    )
    (net (code "110") (name "unconnected-(IC7F-O-Pad6)") (class "Default")
      (node (ref "IC7") (pin "6") (pinfunction "O_6") (pintype "output"))
    )
    (net (code "111") (name "unconnected-(IC14-IP0-Pad8)") (class "Default")
      (node (ref "IC14") (pin "8") (pinfunction "IP0_8") (pintype "input"))
    )
    (net (code "112") (name "unconnected-(IC14-IP1-Pad5)") (class "Default")
      (node (ref "IC14") (pin "5") (pinfunction "IP1_5") (pintype "input"))
    )
    (net (code "113") (name "unconnected-(IC14-IP2-Pad40)") (class "Default")
      (node (ref "IC14") (pin "40") (pinfunction "IP2_40") (pintype "input"))
    )
    (net (code "114") (name "unconnected-(IC14-IP3-Pad3)") (class "Default")
      (node (ref "IC14") (pin "3") (pinfunction "IP3_3") (pintype "input"))
    )
    (net (code "115") (name "unconnected-(IC14-IP4-Pad43)") (class "Default")
      (node (ref "IC14") (pin "43") (pinfunction "IP4_43") (pintype "input"))
    )
    (net (code "116") (name "unconnected-(IC14-IP5-Pad42)") (class "Default")
      (node (ref "IC14") (pin "42") (pinfunction "IP5_42") (pintype "input"))
    )
    (net (code "117") (name "unconnected-(IC14-OP2-Pad31)") (class "Default")
      (node (ref "IC14") (pin "31") (pinfunction "OP2_31") (pintype "output"))
    )
    (net (code "118") (name "unconnected-(IC14-~{IACK}-Pad41)") (class "Default")
      (node (ref "IC14") (pin "41") (pinfunction "~{IACK}_41") (pintype "input"))
    )
    (net (code "119") (name "unconnected-(IC17C-I0-Pad9)") (class "Default")
      (node (ref "IC17") (pin "9") (pinfunction "I0_9") (pintype "input"))
    )
    (net (code "120") (name "unconnected-(IC17C-I1-Pad10)") (class "Default")
      (node (ref "IC17") (pin "10") (pinfunction "I1_10") (pintype "input"))
    )
    (net (code "121") (name "unconnected-(IC17C-O-Pad8)") (class "Default")
      (node (ref "IC17") (pin "8") (pinfunction "O_8") (pintype "output"))
    )
    (net (code "122") (name "unconnected-(IC17D-I0-Pad12)") (class "Default")
      (node (ref "IC17") (pin "12") (pinfunction "I0_12") (pintype "input"))
    )
    (net (code "123") (name "unconnected-(IC17D-I1-Pad13)") (class "Default")
      (node (ref "IC17") (pin "13") (pinfunction "I1_13") (pintype "input"))
    )
    (net (code "124") (name "unconnected-(IC17D-O-Pad11)") (class "Default")
      (node (ref "IC17") (pin "11") (pinfunction "O_11") (pintype "output"))
    )
    (net (code "125") (name "unconnected-(QG1-TS-Pad1)") (class "Default")
      (node (ref "QG1") (pin "1") (pinfunction "TS_1") (pintype "passive"))
    )
    (net (code "126") (name "unconnected-(R5-Pad1)") (class "Default")
      (node (ref "R5") (pin "1") (pinfunction "1_1") (pintype "passive"))
    )
    (net (code "127") (name "unconnected-(R6-Pad1)") (class "Default")
      (node (ref "R6") (pin "1") (pinfunction "1_1") (pintype "passive"))
    )
    (net (code "128") (name "unconnected-(R7-Pad1)") (class "Default")
      (node (ref "R7") (pin "1") (pinfunction "1_1") (pintype "passive"))
    )
    (net (code "129") (name "unconnected-(X1A-B-PadA1)") (class "Default")
      (node (ref "X1") (pin "A1") (pinfunction "B_A1") (pintype "passive"))
    )
    (net (code "130") (name "unconnected-(X1AN-B-PadB16)") (class "Default")
      (node (ref "X1") (pin "B16") (pinfunction "B_B16") (pintype "passive"))
    )
    (net (code "131") (name "unconnected-(X1AP-B-PadB18)") (class "Default")
      (node (ref "X1") (pin "B18") (pinfunction "B_B18") (pintype "passive"))
    )
    (net (code "132") (name "unconnected-(X1AQ-B-PadB19)") (class "Default")
      (node (ref "X1") (pin "B19") (pinfunction "B_B19") (pintype "passive"))
    )
    (net (code "133") (name "unconnected-(X1AS-B-PadB20)") (class "Default")
      (node (ref "X1") (pin "B20") (pinfunction "B_B20") (pintype "passive"))
    )
    (net (code "134") (name "unconnected-(X1BB-B-PadB29)") (class "Default")
      (node (ref "X1") (pin "B29") (pinfunction "B_B29") (pintype "passive"))
    )
    (net (code "135") (name "unconnected-(X1BG-B-PadB4)") (class "Default")
      (node (ref "X1") (pin "B4") (pinfunction "B_B4") (pintype "passive"))
    )
    (net (code "136") (name "unconnected-(X1BH-B-PadB5)") (class "Default")
      (node (ref "X1") (pin "B5") (pinfunction "B_B5") (pintype "passive"))
    )
    (net (code "137") (name "unconnected-(X1BU-B-PadC17)") (class "Default")
      (node (ref "X1") (pin "C17") (pinfunction "B_C17") (pintype "passive"))
    )
    (net (code "138") (name "unconnected-(X1BV-B-PadC18)") (class "Default")
      (node (ref "X1") (pin "C18") (pinfunction "B_C18") (pintype "passive"))
    )
    (net (code "139") (name "unconnected-(X1BW-B-PadC19)") (class "Default")
      (node (ref "X1") (pin "C19") (pinfunction "B_C19") (pintype "passive"))
    )
    (net (code "140") (name "unconnected-(X1BY-B-PadC20)") (class "Default")
      (node (ref "X1") (pin "C20") (pinfunction "B_C20") (pintype "passive"))
    )
    (net (code "141") (name "unconnected-(X1BZ-B-PadC21)") (class "Default")
      (node (ref "X1") (pin "C21") (pinfunction "B_C21") (pintype "passive"))
    )
    (net (code "142") (name "unconnected-(X1CA-B-PadC22)") (class "Default")
      (node (ref "X1") (pin "C22") (pinfunction "B_C22") (pintype "passive"))
    )
    (net (code "143") (name "unconnected-(X1CB-B-PadC23)") (class "Default")
      (node (ref "X1") (pin "C23") (pinfunction "B_C23") (pintype "passive"))
    )
    (net (code "144") (name "unconnected-(X1CC-B-PadC24)") (class "Default")
      (node (ref "X1") (pin "C24") (pinfunction "B_C24") (pintype "passive"))
    )
    (net (code "145") (name "unconnected-(X1CD-B-PadC25)") (class "Default")
      (node (ref "X1") (pin "C25") (pinfunction "B_C25") (pintype "passive"))
    )
    (net (code "146") (name "unconnected-(X1CE-B-PadC26)") (class "Default")
      (node (ref "X1") (pin "C26") (pinfunction "B_C26") (pintype "passive"))
    )
    (net (code "147") (name "unconnected-(X1CF-B-PadC27)") (class "Default")
      (node (ref "X1") (pin "C27") (pinfunction "B_C27") (pintype "passive"))
    )
    (net (code "148") (name "unconnected-(X1CG-B-PadC28)") (class "Default")
      (node (ref "X1") (pin "C28") (pinfunction "B_C28") (pintype "passive"))
    )
    (net (code "149") (name "unconnected-(X1CH-B-PadC29)") (class "Default")
      (node (ref "X1") (pin "C29") (pinfunction "B_C29") (pintype "passive"))
    )
    (net (code "150") (name "unconnected-(X1CJ-B-PadC30)") (class "Default")
      (node (ref "X1") (pin "C30") (pinfunction "B_C30") (pintype "passive"))
    )
    (net (code "151") (name "unconnected-(X1CK-B-PadC31)") (class "Default")
      (node (ref "X1") (pin "C31") (pinfunction "B_C31") (pintype "passive"))
    )
    (net (code "152") (name "unconnected-(X1CL-B-PadC32)") (class "Default")
      (node (ref "X1") (pin "C32") (pinfunction "B_C32") (pintype "passive"))
    )
    (net (code "153") (name "unconnected-(X2-Pad1)") (class "Default")
      (node (ref "X2") (pin "1") (pinfunction "1_1") (pintype "passive"))
    )
    (net (code "154") (name "unconnected-(X2-Pad4)") (class "Default")
      (node (ref "X2") (pin "4") (pinfunction "4_4") (pintype "passive"))
    )
    (net (code "155") (name "unconnected-(X2-Pad6)") (class "Default")
      (node (ref "X2") (pin "6") (pinfunction "6_6") (pintype "passive"))
    )
    (net (code "156") (name "unconnected-(X2-Pad7)") (class "Default")
      (node (ref "X2") (pin "7") (pinfunction "7_7") (pintype "passive"))
    )
    (net (code "157") (name "unconnected-(X2-Pad8)") (class "Default")
      (node (ref "X2") (pin "8") (pinfunction "8_8") (pintype "passive"))
    )
    (net (code "158") (name "unconnected-(X2-Pad9)") (class "Default")
      (node (ref "X2") (pin "9") (pinfunction "9_9") (pintype "passive"))
    )
    (net (code "159") (name "unconnected-(X3-Pad1)") (class "Default")
      (node (ref "X3") (pin "1") (pinfunction "1_1") (pintype "passive"))
    )
    (net (code "160") (name "unconnected-(X3-Pad4)") (class "Default")
      (node (ref "X3") (pin "4") (pinfunction "4_4") (pintype "passive"))
    )
    (net (code "161") (name "unconnected-(X3-Pad6)") (class "Default")
      (node (ref "X3") (pin "6") (pinfunction "6_6") (pintype "passive"))
    )
    (net (code "162") (name "unconnected-(X3-Pad7)") (class "Default")
      (node (ref "X3") (pin "7") (pinfunction "7_7") (pintype "passive"))
    )
    (net (code "163") (name "unconnected-(X3-Pad8)") (class "Default")
      (node (ref "X3") (pin "8") (pinfunction "8_8") (pintype "passive"))
    )
    (net (code "164") (name "unconnected-(X3-Pad9)") (class "Default")
      (node (ref "X3") (pin "9") (pinfunction "9_9") (pintype "passive"))
    )
    (net (code "165") (name "{slash}AS") (class "Default")
      (node (ref "IC3") (pin "18") (pinfunction "G1_18") (pintype "input"))
      (node (ref "IC3") (pin "19") (pinfunction "G2_19") (pintype "input"))
    )
    (net (code "166") (name "~{68681_CS}") (class "Default")
      (node (ref "IC14") (pin "39") (pinfunction "~{CS}_39") (pintype "input"))
      (node (ref "IC17") (pin "3") (pinfunction "O_3") (pintype "output"))
    )
    (net (code "167") (name "~{68681_DTACK}") (class "Default")
      (node (ref "IC14") (pin "10") (pinfunction "~{DTACK}_10") (pintype "output"))
      (node (ref "IC6") (pin "2") (pinfunction "I1_2") (pintype "input"))
      (node (ref "R9") (pin "2") (pinfunction "2_2") (pintype "passive"))
    )
    (net (code "168") (name "~{68681_IRQ}") (class "Default")
      (node (ref "IC14") (pin "24") (pinfunction "~{INTR}_24") (pintype "output"))
      (node (ref "IC5") (pin "2") (pinfunction "5_2") (pintype "input"))
      (node (ref "R5") (pin "2") (pinfunction "2_2") (pintype "passive"))
    )
    (net (code "169") (name "~{A18}") (class "Default")
      (node (ref "IC10") (pin "30") (pinfunction "CE2_30") (pintype "input"))
      (node (ref "IC11") (pin "30") (pinfunction "CE2_30") (pintype "input"))
      (node (ref "IC2") (pin "10") (pinfunction "O_10") (pintype "output"))
      (node (ref "IC8") (pin "30") (pinfunction "CE2_30") (pintype "input"))
      (node (ref "IC9") (pin "30") (pinfunction "CE2_30") (pintype "input"))
    )
    (net (code "170") (name "~{A19}") (class "Default")
      (node (ref "IC17") (pin "2") (pinfunction "I1_2") (pintype "input"))
      (node (ref "IC2") (pin "6") (pinfunction "O_6") (pintype "output"))
    )
    (net (code "171") (name "~{AS}") (class "Default")
      (node (ref "IC1") (pin "6") (pinfunction "AS_6") (pintype "output"))
      (node (ref "X1") (pin "B21") (pinfunction "B_B21") (pintype "passive"))
    )
    (net (code "172") (name "~{BERR}") (class "Default")
      (node (ref "IC1") (pin "24") (pinfunction "BERR_24") (pintype "input"))
      (node (ref "X1") (pin "B9") (pinfunction "B_B9") (pintype "passive"))
    )
    (net (code "173") (name "~{BGACK}") (class "Default")
      (node (ref "IC1") (pin "12") (pinfunction "BGACK_12") (pintype "input"))
      (node (ref "X1") (pin "B15") (pinfunction "B_B15") (pintype "passive"))
    )
    (net (code "174") (name "~{BG}") (class "Default")
      (node (ref "IC1") (pin "11") (pinfunction "BG_11") (pintype "output"))
      (node (ref "X1") (pin "B14") (pinfunction "B_B14") (pintype "passive"))
    )
    (net (code "175") (name "~{BR}") (class "Default")
      (node (ref "IC1") (pin "13") (pinfunction "BR_13") (pintype "input"))
      (node (ref "X1") (pin "B13") (pinfunction "B_B13") (pintype "passive"))
    )
    (net (code "176") (name "~{DTACK}") (class "Default")
      (node (ref "IC1") (pin "10") (pinfunction "DTACK_10") (pintype "input"))
      (node (ref "IC2") (pin "8") (pinfunction "O_8") (pintype "output"))
    )
    (net (code "177") (name "~{EXT_DTACK}") (class "Default")
      (node (ref "IC6") (pin "1") (pinfunction "I0_1") (pintype "input"))
      (node (ref "R8") (pin "2") (pinfunction "2_2") (pintype "passive"))
      (node (ref "X1") (pin "B28") (pinfunction "B_B28") (pintype "passive"))
    )
    (net (code "178") (name "~{EXT_IRQ}") (class "Default")
      (node (ref "IC5") (pin "1") (pinfunction "4_1") (pintype "input"))
      (node (ref "R4") (pin "2") (pinfunction "2_2") (pintype "passive"))
      (node (ref "X1") (pin "B17") (pinfunction "B_B17") (pintype "passive"))
    )
    (net (code "179") (name "~{HALT}") (class "Default")
      (node (ref "IC1") (pin "19") (pinfunction "HALT_19") (pintype "bidirectional"))
      (node (ref "IC7") (pin "10") (pinfunction "O_10") (pintype "output"))
      (node (ref "LED2") (pin "C") (pinfunction "C_C") (pintype "passive"))
      (node (ref "X1") (pin "B11") (pinfunction "B_B11") (pintype "passive"))
    )
    (net (code "180") (name "~{IPL0}") (class "Default")
      (node (ref "IC1") (pin "27") (pinfunction "IPL0_27") (pintype "input"))
      (node (ref "IC5") (pin "9") (pinfunction "A0_9") (pintype "output"))
    )
    (net (code "181") (name "~{IPL1}") (class "Default")
      (node (ref "IC1") (pin "26") (pinfunction "IPL1_26") (pintype "input"))
      (node (ref "IC5") (pin "7") (pinfunction "A1_7") (pintype "output"))
    )
    (net (code "182") (name "~{IPL2}") (class "Default")
      (node (ref "IC1") (pin "25") (pinfunction "IPL2_25") (pintype "input"))
      (node (ref "IC5") (pin "6") (pinfunction "A2_6") (pintype "output"))
    )
    (net (code "183") (name "~{LDS}") (class "Default")
      (node (ref "IC1") (pin "8") (pinfunction "LDS_8") (pintype "output"))
      (node (ref "X1") (pin "B24") (pinfunction "B_B24") (pintype "passive"))
    )
    (net (code "184") (name "~{NMI}") (class "Default")
      (node (ref "IC5") (pin "4") (pinfunction "7_4") (pintype "input"))
      (node (ref "IC7") (pin "12") (pinfunction "O_12") (pintype "output"))
      (node (ref "R7") (pin "2") (pinfunction "2_2") (pintype "passive"))
    )
    (net (code "185") (name "~{OE}") (class "Default")
      (node (ref "IC10") (pin "24") (pinfunction "~{OE}_24") (pintype "input"))
      (node (ref "IC11") (pin "24") (pinfunction "~{OE}_24") (pintype "input"))
      (node (ref "IC12") (pin "24") (pinfunction "~{OE}_24") (pintype "input"))
      (node (ref "IC13") (pin "24") (pinfunction "~{OE}_24") (pintype "input"))
      (node (ref "IC15") (pin "22") (pinfunction "~{OE}_22") (pintype "input"))
      (node (ref "IC2") (pin "2") (pinfunction "O_2") (pintype "output"))
      (node (ref "IC8") (pin "24") (pinfunction "~{OE}_24") (pintype "input"))
      (node (ref "IC9") (pin "24") (pinfunction "~{OE}_24") (pintype "input"))
    )
    (net (code "186") (name "~{REGION0}") (class "Default")
      (node (ref "IC12") (pin "22") (pinfunction "~{CS}_22") (pintype "input"))
      (node (ref "IC13") (pin "22") (pinfunction "~{CS}_22") (pintype "input"))
      (node (ref "IC3") (pin "1") (pinfunction "0_1") (pintype "output"))
      (node (ref "IC6") (pin "3") (pinfunction "I2_3") (pintype "input"))
    )
    (net (code "187") (name "~{REGION1}") (class "Default")
      (node (ref "IC10") (pin "22") (pinfunction "~{CE1}_22") (pintype "input"))
      (node (ref "IC11") (pin "22") (pinfunction "~{CE1}_22") (pintype "input"))
      (node (ref "IC3") (pin "2") (pinfunction "1_2") (pintype "output"))
      (node (ref "IC6") (pin "4") (pinfunction "I3_4") (pintype "input"))
      (node (ref "IC8") (pin "22") (pinfunction "~{CE1}_22") (pintype "input"))
      (node (ref "IC9") (pin "22") (pinfunction "~{CE1}_22") (pintype "input"))
    )
    (net (code "188") (name "~{REGION15}") (class "Default")
      (node (ref "IC2") (pin "3") (pinfunction "I_3") (pintype "input"))
      (node (ref "IC3") (pin "17") (pinfunction "15_17") (pintype "output"))
    )
    (net (code "189") (name "~{RESET}") (class "Default")
      (node (ref "IC1") (pin "20") (pinfunction "RESET_20") (pintype "bidirectional"))
      (node (ref "IC14") (pin "38") (pinfunction "~{RESET}_38") (pintype "input"))
      (node (ref "IC7") (pin "8") (pinfunction "O_8") (pintype "output"))
      (node (ref "LED3") (pin "C") (pinfunction "C_C") (pintype "passive"))
      (node (ref "X1") (pin "B10") (pinfunction "B_B10") (pintype "passive"))
    )
    (net (code "190") (name "~{RTC_CS}") (class "Default")
      (node (ref "IC15") (pin "20") (pinfunction "~{CS}_20") (pintype "input"))
      (node (ref "IC17") (pin "6") (pinfunction "O_6") (pintype "output"))
      (node (ref "IC6") (pin "5") (pinfunction "I4_5") (pintype "input"))
    )
    (net (code "191") (name "~{TIMER_IRQ}") (class "Default")
      (node (ref "IC5") (pin "3") (pinfunction "6_3") (pintype "input"))
      (node (ref "R6") (pin "2") (pinfunction "2_2") (pintype "passive"))
    )
    (net (code "192") (name "~{UDS}") (class "Default")
      (node (ref "IC1") (pin "7") (pinfunction "UDS_7") (pintype "output"))
      (node (ref "X1") (pin "B23") (pinfunction "B_B23") (pintype "passive"))
    )
    (net (code "193") (name "~{VPA}") (class "Default")
      (node (ref "IC1") (pin "23") (pinfunction "VPA_23") (pintype "input"))
      (node (ref "IC4") (pin "8") (pinfunction "O_8") (pintype "output"))
      (node (ref "X1") (pin "B12") (pinfunction "B_B12") (pintype "passive"))
    )
  )
)
